# slimarm_apricot.net
KiCad netlist of a schematic drawn in EasyEDA Pro
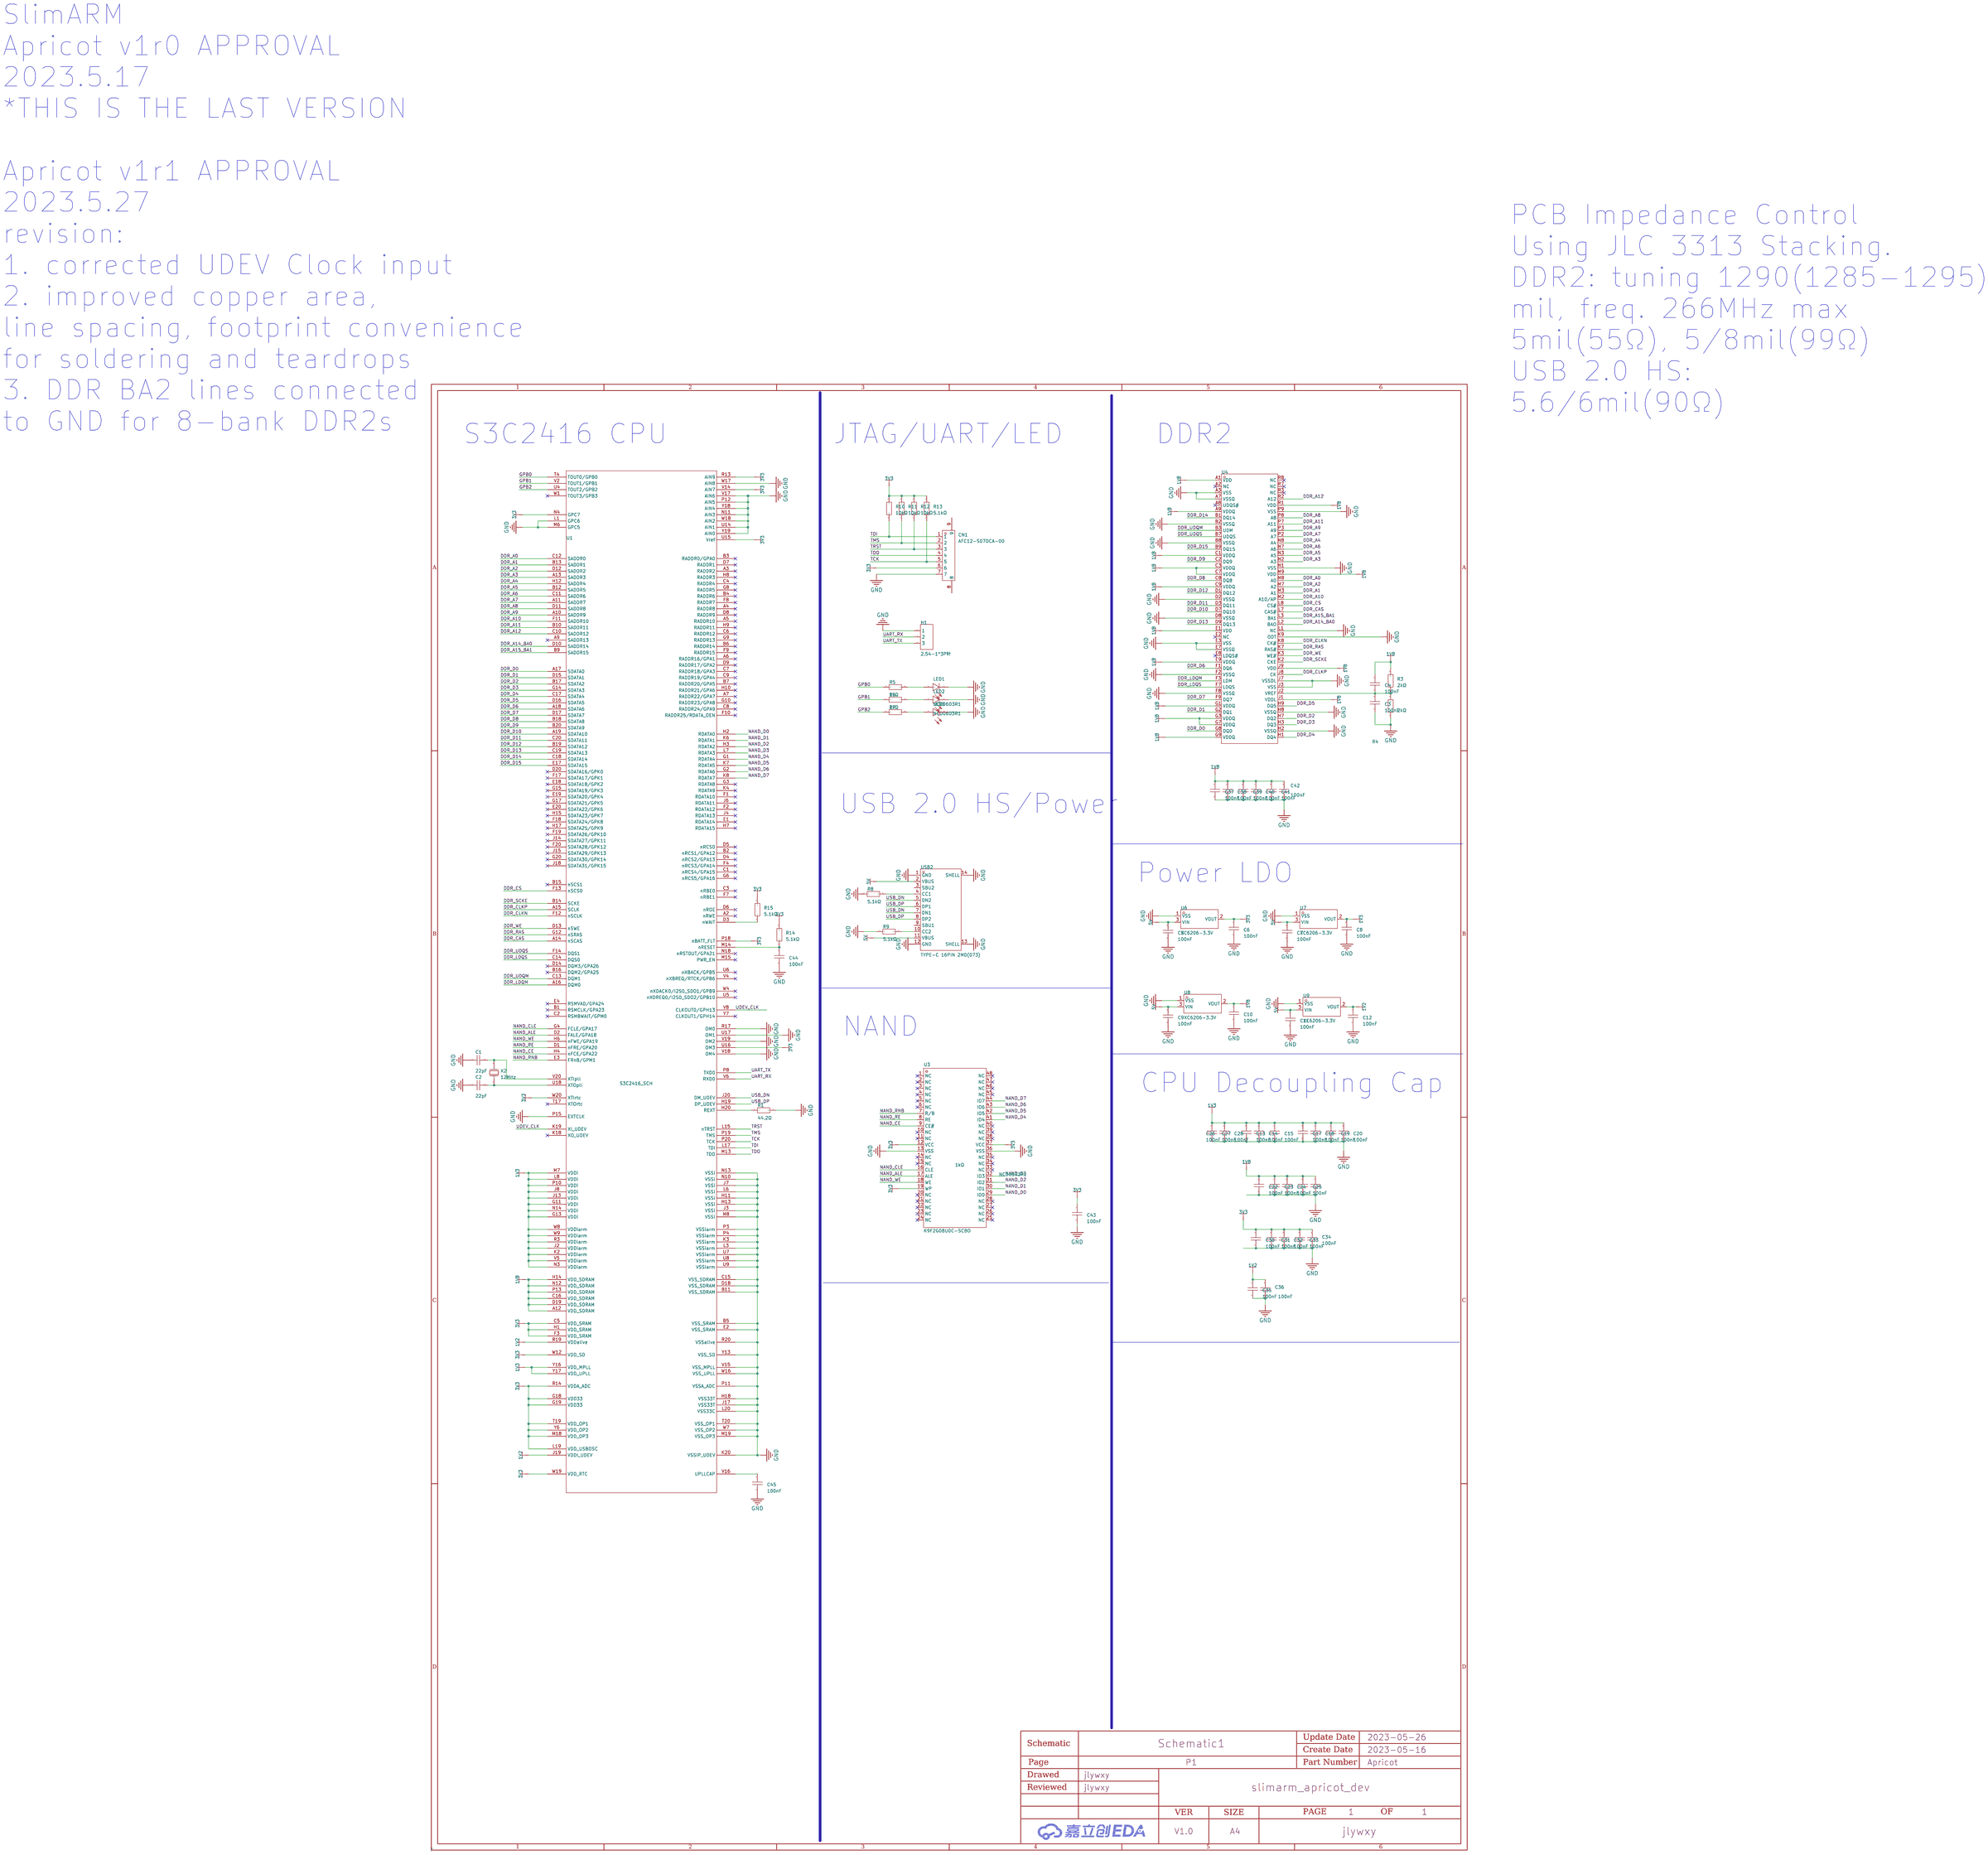
[diagram p0: schematic sheet]

(export (version "E")
  (design (tool "Eeschema 10.0.6"))
  (components
    (comp (ref "C1")
      (value "22pF")
      (footprint "easyedapro:C0402")
      (description "容值:22pF;精度:±5%;额定电压:50V;材质(温度系数):NP0;")
      (fields
        (field (name "Manufacturer Part") "CC0402JRNPO9BN220")
        (field (name "Manufacturer") "YAGEO(国巨)")
      )
      (libsource (lib "easyedapro") (part "CC0402JRNPO9BN220"))
    )
    (comp (ref "C2")
      (value "22pF")
      (footprint "easyedapro:C0402")
      (description "容值:22pF;精度:±5%;额定电压:50V;材质(温度系数):NP0;")
      (fields
        (field (name "Manufacturer Part") "CC0402JRNPO9BN220")
        (field (name "Manufacturer") "YAGEO(国巨)")
      )
      (libsource (lib "easyedapro") (part "CC0402JRNPO9BN220"))
    )
    (comp (ref "C3")
      (value "100nF")
      (footprint "easyedapro:C0402")
      (description "容值:22pF;精度:±5%;额定电压:50V;材质(温度系数):NP0;")
      (fields
        (field (name "Manufacturer Part") "CC0402JRNPO9BN220")
        (field (name "Manufacturer") "YAGEO(国巨)")
      )
      (libsource (lib "easyedapro") (part "CC0402JRNPO9BN220"))
    )
    (comp (ref "C4")
      (value "100nF")
      (footprint "easyedapro:C0402")
      (description "容值:22pF;精度:±5%;额定电压:50V;材质(温度系数):NP0;")
      (fields
        (field (name "Manufacturer Part") "CC0402JRNPO9BN220")
        (field (name "Manufacturer") "YAGEO(国巨)")
      )
      (libsource (lib "easyedapro") (part "CC0402JRNPO9BN220"))
    )
    (comp (ref "C5")
      (value "100nF")
      (footprint "easyedapro:C0402")
      (description "容值:22pF;精度:±5%;额定电压:50V;材质(温度系数):NP0;")
      (fields
        (field (name "Manufacturer Part") "CC0402JRNPO9BN220")
        (field (name "Manufacturer") "YAGEO(国巨)")
      )
      (libsource (lib "easyedapro") (part "CC0402JRNPO9BN220"))
    )
    (comp (ref "C6")
      (value "100nF")
      (footprint "easyedapro:C0402")
      (description "容值:22pF;精度:±5%;额定电压:50V;材质(温度系数):NP0;")
      (fields
        (field (name "Manufacturer Part") "CC0402JRNPO9BN220")
        (field (name "Manufacturer") "YAGEO(国巨)")
      )
      (libsource (lib "easyedapro") (part "CC0402JRNPO9BN220"))
    )
    (comp (ref "C7")
      (value "100nF")
      (footprint "easyedapro:C0402")
      (description "容值:22pF;精度:±5%;额定电压:50V;材质(温度系数):NP0;")
      (fields
        (field (name "Manufacturer Part") "CC0402JRNPO9BN220")
        (field (name "Manufacturer") "YAGEO(国巨)")
      )
      (libsource (lib "easyedapro") (part "CC0402JRNPO9BN220"))
    )
    (comp (ref "C8")
      (value "100nF")
      (footprint "easyedapro:C0402")
      (description "容值:22pF;精度:±5%;额定电压:50V;材质(温度系数):NP0;")
      (fields
        (field (name "Manufacturer Part") "CC0402JRNPO9BN220")
        (field (name "Manufacturer") "YAGEO(国巨)")
      )
      (libsource (lib "easyedapro") (part "CC0402JRNPO9BN220"))
    )
    (comp (ref "C9")
      (value "100nF")
      (footprint "easyedapro:C0402")
      (description "容值:22pF;精度:±5%;额定电压:50V;材质(温度系数):NP0;")
      (fields
        (field (name "Manufacturer Part") "CC0402JRNPO9BN220")
        (field (name "Manufacturer") "YAGEO(国巨)")
      )
      (libsource (lib "easyedapro") (part "CC0402JRNPO9BN220"))
    )
    (comp (ref "C10")
      (value "100nF")
      (footprint "easyedapro:C0402")
      (description "容值:22pF;精度:±5%;额定电压:50V;材质(温度系数):NP0;")
      (fields
        (field (name "Manufacturer Part") "CC0402JRNPO9BN220")
        (field (name "Manufacturer") "YAGEO(国巨)")
      )
      (libsource (lib "easyedapro") (part "CC0402JRNPO9BN220"))
    )
    (comp (ref "C11")
      (value "100nF")
      (footprint "easyedapro:C0402")
      (description "容值:22pF;精度:±5%;额定电压:50V;材质(温度系数):NP0;")
      (fields
        (field (name "Manufacturer Part") "CC0402JRNPO9BN220")
        (field (name "Manufacturer") "YAGEO(国巨)")
      )
      (libsource (lib "easyedapro") (part "CC0402JRNPO9BN220"))
    )
    (comp (ref "C12")
      (value "100nF")
      (footprint "easyedapro:C0402")
      (description "容值:22pF;精度:±5%;额定电压:50V;材质(温度系数):NP0;")
      (fields
        (field (name "Manufacturer Part") "CC0402JRNPO9BN220")
        (field (name "Manufacturer") "YAGEO(国巨)")
      )
      (libsource (lib "easyedapro") (part "CC0402JRNPO9BN220"))
    )
    (comp (ref "C13")
      (value "100nF")
      (footprint "easyedapro:C0402")
      (description "容值:22pF;精度:±5%;额定电压:50V;材质(温度系数):NP0;")
      (fields
        (field (name "Manufacturer Part") "CC0402JRNPO9BN220")
        (field (name "Manufacturer") "YAGEO(国巨)")
      )
      (libsource (lib "easyedapro") (part "CC0402JRNPO9BN220"))
    )
    (comp (ref "C14")
      (value "100nF")
      (footprint "easyedapro:C0402")
      (description "容值:22pF;精度:±5%;额定电压:50V;材质(温度系数):NP0;")
      (fields
        (field (name "Manufacturer Part") "CC0402JRNPO9BN220")
        (field (name "Manufacturer") "YAGEO(国巨)")
      )
      (libsource (lib "easyedapro") (part "CC0402JRNPO9BN220"))
    )
    (comp (ref "C15")
      (value "100nF")
      (footprint "easyedapro:C0402")
      (description "容值:22pF;精度:±5%;额定电压:50V;材质(温度系数):NP0;")
      (fields
        (field (name "Manufacturer Part") "CC0402JRNPO9BN220")
        (field (name "Manufacturer") "YAGEO(国巨)")
      )
      (libsource (lib "easyedapro") (part "CC0402JRNPO9BN220"))
    )
    (comp (ref "C17")
      (value "100nF")
      (footprint "easyedapro:C0402")
      (description "容值:22pF;精度:±5%;额定电压:50V;材质(温度系数):NP0;")
      (fields
        (field (name "Manufacturer Part") "CC0402JRNPO9BN220")
        (field (name "Manufacturer") "YAGEO(国巨)")
      )
      (libsource (lib "easyedapro") (part "CC0402JRNPO9BN220"))
    )
    (comp (ref "C18")
      (value "100nF")
      (footprint "easyedapro:C0402")
      (description "容值:22pF;精度:±5%;额定电压:50V;材质(温度系数):NP0;")
      (fields
        (field (name "Manufacturer Part") "CC0402JRNPO9BN220")
        (field (name "Manufacturer") "YAGEO(国巨)")
      )
      (libsource (lib "easyedapro") (part "CC0402JRNPO9BN220"))
    )
    (comp (ref "C19")
      (value "100nF")
      (footprint "easyedapro:C0402")
      (description "容值:22pF;精度:±5%;额定电压:50V;材质(温度系数):NP0;")
      (fields
        (field (name "Manufacturer Part") "CC0402JRNPO9BN220")
        (field (name "Manufacturer") "YAGEO(国巨)")
      )
      (libsource (lib "easyedapro") (part "CC0402JRNPO9BN220"))
    )
    (comp (ref "C20")
      (value "100nF")
      (footprint "easyedapro:C0402")
      (description "容值:22pF;精度:±5%;额定电压:50V;材质(温度系数):NP0;")
      (fields
        (field (name "Manufacturer Part") "CC0402JRNPO9BN220")
        (field (name "Manufacturer") "YAGEO(国巨)")
      )
      (libsource (lib "easyedapro") (part "CC0402JRNPO9BN220"))
    )
    (comp (ref "C22")
      (value "100nF")
      (footprint "easyedapro:C0402")
      (description "容值:22pF;精度:±5%;额定电压:50V;材质(温度系数):NP0;")
      (fields
        (field (name "Manufacturer Part") "CC0402JRNPO9BN220")
        (field (name "Manufacturer") "YAGEO(国巨)")
      )
      (libsource (lib "easyedapro") (part "CC0402JRNPO9BN220"))
    )
    (comp (ref "C23")
      (value "100nF")
      (footprint "easyedapro:C0402")
      (description "容值:22pF;精度:±5%;额定电压:50V;材质(温度系数):NP0;")
      (fields
        (field (name "Manufacturer Part") "CC0402JRNPO9BN220")
        (field (name "Manufacturer") "YAGEO(国巨)")
      )
      (libsource (lib "easyedapro") (part "CC0402JRNPO9BN220"))
    )
    (comp (ref "C24")
      (value "100nF")
      (footprint "easyedapro:C0402")
      (description "容值:22pF;精度:±5%;额定电压:50V;材质(温度系数):NP0;")
      (fields
        (field (name "Manufacturer Part") "CC0402JRNPO9BN220")
        (field (name "Manufacturer") "YAGEO(国巨)")
      )
      (libsource (lib "easyedapro") (part "CC0402JRNPO9BN220"))
    )
    (comp (ref "C25")
      (value "100nF")
      (footprint "easyedapro:C0402")
      (description "容值:22pF;精度:±5%;额定电压:50V;材质(温度系数):NP0;")
      (fields
        (field (name "Manufacturer Part") "CC0402JRNPO9BN220")
        (field (name "Manufacturer") "YAGEO(国巨)")
      )
      (libsource (lib "easyedapro") (part "CC0402JRNPO9BN220"))
    )
    (comp (ref "C26")
      (value "100nF")
      (footprint "easyedapro:C0402")
      (description "容值:22pF;精度:±5%;额定电压:50V;材质(温度系数):NP0;")
      (fields
        (field (name "Manufacturer Part") "CC0402JRNPO9BN220")
        (field (name "Manufacturer") "YAGEO(国巨)")
      )
      (libsource (lib "easyedapro") (part "CC0402JRNPO9BN220"))
    )
    (comp (ref "C27")
      (value "100nF")
      (footprint "easyedapro:C0402")
      (description "容值:22pF;精度:±5%;额定电压:50V;材质(温度系数):NP0;")
      (fields
        (field (name "Manufacturer Part") "CC0402JRNPO9BN220")
        (field (name "Manufacturer") "YAGEO(国巨)")
      )
      (libsource (lib "easyedapro") (part "CC0402JRNPO9BN220"))
    )
    (comp (ref "C28")
      (value "100nF")
      (footprint "easyedapro:C0402")
      (description "容值:22pF;精度:±5%;额定电压:50V;材质(温度系数):NP0;")
      (fields
        (field (name "Manufacturer Part") "CC0402JRNPO9BN220")
        (field (name "Manufacturer") "YAGEO(国巨)")
      )
      (libsource (lib "easyedapro") (part "CC0402JRNPO9BN220"))
    )
    (comp (ref "C30")
      (value "100nF")
      (footprint "easyedapro:C0402")
      (description "容值:22pF;精度:±5%;额定电压:50V;材质(温度系数):NP0;")
      (fields
        (field (name "Manufacturer Part") "CC0402JRNPO9BN220")
        (field (name "Manufacturer") "YAGEO(国巨)")
      )
      (libsource (lib "easyedapro") (part "CC0402JRNPO9BN220"))
    )
    (comp (ref "C31")
      (value "100nF")
      (footprint "easyedapro:C0402")
      (description "容值:22pF;精度:±5%;额定电压:50V;材质(温度系数):NP0;")
      (fields
        (field (name "Manufacturer Part") "CC0402JRNPO9BN220")
        (field (name "Manufacturer") "YAGEO(国巨)")
      )
      (libsource (lib "easyedapro") (part "CC0402JRNPO9BN220"))
    )
    (comp (ref "C32")
      (value "100nF")
      (footprint "easyedapro:C0402")
      (description "容值:22pF;精度:±5%;额定电压:50V;材质(温度系数):NP0;")
      (fields
        (field (name "Manufacturer Part") "CC0402JRNPO9BN220")
        (field (name "Manufacturer") "YAGEO(国巨)")
      )
      (libsource (lib "easyedapro") (part "CC0402JRNPO9BN220"))
    )
    (comp (ref "C33")
      (value "100nF")
      (footprint "easyedapro:C0402")
      (description "容值:22pF;精度:±5%;额定电压:50V;材质(温度系数):NP0;")
      (fields
        (field (name "Manufacturer Part") "CC0402JRNPO9BN220")
        (field (name "Manufacturer") "YAGEO(国巨)")
      )
      (libsource (lib "easyedapro") (part "CC0402JRNPO9BN220"))
    )
    (comp (ref "C34")
      (value "100nF")
      (footprint "easyedapro:C0402")
      (description "容值:22pF;精度:±5%;额定电压:50V;材质(温度系数):NP0;")
      (fields
        (field (name "Manufacturer Part") "CC0402JRNPO9BN220")
        (field (name "Manufacturer") "YAGEO(国巨)")
      )
      (libsource (lib "easyedapro") (part "CC0402JRNPO9BN220"))
    )
    (comp (ref "C35")
      (value "100nF")
      (footprint "easyedapro:C0402")
      (description "容值:22pF;精度:±5%;额定电压:50V;材质(温度系数):NP0;")
      (fields
        (field (name "Manufacturer Part") "CC0402JRNPO9BN220")
        (field (name "Manufacturer") "YAGEO(国巨)")
      )
      (libsource (lib "easyedapro") (part "CC0402JRNPO9BN220"))
    )
    (comp (ref "C36")
      (value "100nF")
      (footprint "easyedapro:C0402")
      (description "容值:22pF;精度:±5%;额定电压:50V;材质(温度系数):NP0;")
      (fields
        (field (name "Manufacturer Part") "CC0402JRNPO9BN220")
        (field (name "Manufacturer") "YAGEO(国巨)")
      )
      (libsource (lib "easyedapro") (part "CC0402JRNPO9BN220"))
    )
    (comp (ref "C37")
      (value "100nF")
      (footprint "easyedapro:C0402")
      (description "容值:22pF;精度:±5%;额定电压:50V;材质(温度系数):NP0;")
      (fields
        (field (name "Manufacturer Part") "CC0402JRNPO9BN220")
        (field (name "Manufacturer") "YAGEO(国巨)")
      )
      (libsource (lib "easyedapro") (part "CC0402JRNPO9BN220"))
    )
    (comp (ref "C38")
      (value "100nF")
      (footprint "easyedapro:C0402")
      (description "容值:22pF;精度:±5%;额定电压:50V;材质(温度系数):NP0;")
      (fields
        (field (name "Manufacturer Part") "CC0402JRNPO9BN220")
        (field (name "Manufacturer") "YAGEO(国巨)")
      )
      (libsource (lib "easyedapro") (part "CC0402JRNPO9BN220"))
    )
    (comp (ref "C39")
      (value "100nF")
      (footprint "easyedapro:C0402")
      (description "容值:22pF;精度:±5%;额定电压:50V;材质(温度系数):NP0;")
      (fields
        (field (name "Manufacturer Part") "CC0402JRNPO9BN220")
        (field (name "Manufacturer") "YAGEO(国巨)")
      )
      (libsource (lib "easyedapro") (part "CC0402JRNPO9BN220"))
    )
    (comp (ref "C40")
      (value "100nF")
      (footprint "easyedapro:C0402")
      (description "容值:22pF;精度:±5%;额定电压:50V;材质(温度系数):NP0;")
      (fields
        (field (name "Manufacturer Part") "CC0402JRNPO9BN220")
        (field (name "Manufacturer") "YAGEO(国巨)")
      )
      (libsource (lib "easyedapro") (part "CC0402JRNPO9BN220"))
    )
    (comp (ref "C41")
      (value "100nF")
      (footprint "easyedapro:C0402")
      (description "容值:22pF;精度:±5%;额定电压:50V;材质(温度系数):NP0;")
      (fields
        (field (name "Manufacturer Part") "CC0402JRNPO9BN220")
        (field (name "Manufacturer") "YAGEO(国巨)")
      )
      (libsource (lib "easyedapro") (part "CC0402JRNPO9BN220"))
    )
    (comp (ref "C42")
      (value "100nF")
      (footprint "easyedapro:C0402")
      (description "容值:22pF;精度:±5%;额定电压:50V;材质(温度系数):NP0;")
      (fields
        (field (name "Manufacturer Part") "CC0402JRNPO9BN220")
        (field (name "Manufacturer") "YAGEO(国巨)")
      )
      (libsource (lib "easyedapro") (part "CC0402JRNPO9BN220"))
    )
    (comp (ref "C43")
      (value "100nF")
      (footprint "easyedapro:C0402")
      (description "容值:22pF;精度:±5%;额定电压:50V;材质(温度系数):NP0;")
      (fields
        (field (name "Manufacturer Part") "CC0402JRNPO9BN220")
        (field (name "Manufacturer") "YAGEO(国巨)")
      )
      (libsource (lib "easyedapro") (part "CC0402JRNPO9BN220"))
    )
    (comp (ref "C44")
      (value "100nF")
      (footprint "easyedapro:C0402")
      (description "容值:22pF;精度:±5%;额定电压:50V;材质(温度系数):NP0;")
      (fields
        (field (name "Manufacturer Part") "CC0402JRNPO9BN220")
        (field (name "Manufacturer") "YAGEO(国巨)")
      )
      (libsource (lib "easyedapro") (part "CC0402JRNPO9BN220"))
    )
    (comp (ref "C45")
      (value "100nF")
      (footprint "easyedapro:C0402")
      (description "容值:22pF;精度:±5%;额定电压:50V;材质(温度系数):NP0;")
      (fields
        (field (name "Manufacturer Part") "CC0402JRNPO9BN220")
        (field (name "Manufacturer") "YAGEO(国巨)")
      )
      (libsource (lib "easyedapro") (part "CC0402JRNPO9BN220"))
    )
    (comp (ref "CN1")
      (value "AFC12-S07DCA-00")
      (footprint "easyedapro:CONN-SMD_AFC12-S07DCA-00")
      (description "参考系列:-;间距:1.25mm;插针结构:1x7P;排数:1;每排PIN数:7;行距:-;公母:公型插针;安装方式:卧贴;额定电流:1A;工作温度范围:-20°C~+85°C;")
      (fields (field (name "Manufacturer") "JS(钜硕电子)"))
      (libsource (lib "easyedapro") (part "AFC12-S07DCA-00"))
    )
    (comp (ref "H1")
      (value "2.54-1*3P针")
      (footprint "easyedapro:HDR-TH_3P-P2.54-V-M-1")
      (fields (field (name "Manufacturer") "BOOMELE(博穆精密)"))
      (libsource (lib "easyedapro") (part "Header-Male-2.54_1x3"))
    )
    (comp (ref "LED1")
      (value "NCD0603R1")
      (footprint "easyedapro:LED0603-RD_RED")
      (description "发光颜色:红灯;")
      (fields (field (name "Manufacturer") "国星光电"))
      (libsource (lib "easyedapro") (part "FC-DA1608HRK-620D"))
    )
    (comp (ref "LED2")
      (value "NCD0603R1")
      (footprint "easyedapro:LED0603-RD_RED")
      (description "发光颜色:红灯;")
      (fields (field (name "Manufacturer") "国星光电"))
      (libsource (lib "easyedapro") (part "FC-DA1608HRK-620D"))
    )
    (comp (ref "LED3")
      (value "NCD0603R1")
      (footprint "easyedapro:LED0603-RD_RED")
      (description "发光颜色:红灯;")
      (fields (field (name "Manufacturer") "国星光电"))
      (libsource (lib "easyedapro") (part "FC-DA1608HRK-620D"))
    )
    (comp (ref "R1")
      (value "44.2Ω")
      (footprint "easyedapro:R0402")
      (description "阻值:44.2Ω;精度:±1%;功率:62.5mW;")
      (fields (field (name "Manufacturer Part") "RCT0244R2FLF") (field (name "Manufacturer") "HKR"))
      (libsource (lib "easyedapro") (part "RCT0244R2FLF"))
    )
    (comp (ref "R3")
      (value "2kΩ")
      (footprint "easyedapro:R0402")
      (description "阻值:44.2Ω;精度:±1%;功率:62.5mW;")
      (fields (field (name "Manufacturer Part") "RCT0244R2FLF") (field (name "Manufacturer") "HKR"))
      (libsource (lib "easyedapro") (part "RCT0244R2FLF"))
    )
    (comp (ref "R4")
      (value "2kΩ")
      (footprint "easyedapro:R0402")
      (description "阻值:44.2Ω;精度:±1%;功率:62.5mW;")
      (fields (field (name "Manufacturer Part") "RCT0244R2FLF") (field (name "Manufacturer") "HKR"))
      (libsource (lib "easyedapro") (part "RCT0244R2FLF"))
    )
    (comp (ref "R5")
      (value "1kΩ")
      (footprint "easyedapro:R0603")
      (description "电阻类型:厚膜电阻;阻值:1kΩ;精度:±1%;功率:100mW;")
      (fields
        (field (name "Manufacturer Part") "0603WAF1001T5E")
        (field (name "Manufacturer") "UNI-ROYAL(厚声)")
      )
      (libsource (lib "easyedapro") (part "0603WAF1001T5E"))
    )
    (comp (ref "R6")
      (value "1kΩ")
      (footprint "easyedapro:R0603")
      (description "电阻类型:厚膜电阻;阻值:1kΩ;精度:±1%;功率:100mW;")
      (fields
        (field (name "Manufacturer Part") "0603WAF1001T5E")
        (field (name "Manufacturer") "UNI-ROYAL(厚声)")
      )
      (libsource (lib "easyedapro") (part "0603WAF1001T5E"))
    )
    (comp (ref "R7")
      (value "1kΩ")
      (footprint "easyedapro:R0603")
      (description "电阻类型:厚膜电阻;阻值:1kΩ;精度:±1%;功率:100mW;")
      (fields
        (field (name "Manufacturer Part") "0603WAF1001T5E")
        (field (name "Manufacturer") "UNI-ROYAL(厚声)")
      )
      (libsource (lib "easyedapro") (part "0603WAF1001T5E"))
    )
    (comp (ref "R8")
      (value "5.1kΩ")
      (footprint "easyedapro:R0402")
      (description "电阻类型:厚膜电阻;阻值:5.1kΩ;精度:±1%;功率:62.5mW;")
      (fields
        (field (name "Manufacturer Part") "0402WGF5101TCE")
        (field (name "Manufacturer") "UNI-ROYAL(厚声)")
      )
      (libsource (lib "easyedapro") (part "0402WGF5101TCE"))
    )
    (comp (ref "R9")
      (value "5.1kΩ")
      (footprint "easyedapro:R0402")
      (description "电阻类型:厚膜电阻;阻值:5.1kΩ;精度:±1%;功率:62.5mW;")
      (fields
        (field (name "Manufacturer Part") "0402WGF5101TCE")
        (field (name "Manufacturer") "UNI-ROYAL(厚声)")
      )
      (libsource (lib "easyedapro") (part "0402WGF5101TCE"))
    )
    (comp (ref "R10")
      (value "10kΩ")
      (footprint "easyedapro:R0402")
      (description "电阻类型:厚膜电阻;阻值:5.1kΩ;精度:±1%;功率:62.5mW;")
      (fields
        (field (name "Manufacturer Part") "0402WGF5101TCE")
        (field (name "Manufacturer") "UNI-ROYAL(厚声)")
      )
      (libsource (lib "easyedapro") (part "0402WGF5101TCE"))
    )
    (comp (ref "R11")
      (value "10kΩ")
      (footprint "easyedapro:R0402")
      (description "电阻类型:厚膜电阻;阻值:5.1kΩ;精度:±1%;功率:62.5mW;")
      (fields
        (field (name "Manufacturer Part") "0402WGF5101TCE")
        (field (name "Manufacturer") "UNI-ROYAL(厚声)")
      )
      (libsource (lib "easyedapro") (part "0402WGF5101TCE"))
    )
    (comp (ref "R12")
      (value "10kΩ")
      (footprint "easyedapro:R0402")
      (description "电阻类型:厚膜电阻;阻值:5.1kΩ;精度:±1%;功率:62.5mW;")
      (fields
        (field (name "Manufacturer Part") "0402WGF5101TCE")
        (field (name "Manufacturer") "UNI-ROYAL(厚声)")
      )
      (libsource (lib "easyedapro") (part "0402WGF5101TCE"))
    )
    (comp (ref "R13")
      (value "5.1kΩ")
      (footprint "easyedapro:R0402")
      (description "电阻类型:厚膜电阻;阻值:5.1kΩ;精度:±1%;功率:62.5mW;")
      (fields
        (field (name "Manufacturer Part") "0402WGF5101TCE")
        (field (name "Manufacturer") "UNI-ROYAL(厚声)")
      )
      (libsource (lib "easyedapro") (part "0402WGF5101TCE"))
    )
    (comp (ref "R14")
      (value "5.1kΩ")
      (footprint "easyedapro:R0402")
      (description "电阻类型:厚膜电阻;阻值:5.1kΩ;精度:±1%;功率:62.5mW;")
      (fields
        (field (name "Manufacturer Part") "0402WGF5101TCE")
        (field (name "Manufacturer") "UNI-ROYAL(厚声)")
      )
      (libsource (lib "easyedapro") (part "0402WGF5101TCE"))
    )
    (comp (ref "R15")
      (value "5.1kΩ")
      (footprint "easyedapro:R0402")
      (description "电阻类型:厚膜电阻;阻值:5.1kΩ;精度:±1%;功率:62.5mW;")
      (fields
        (field (name "Manufacturer Part") "0402WGF5101TCE")
        (field (name "Manufacturer") "UNI-ROYAL(厚声)")
      )
      (libsource (lib "easyedapro") (part "0402WGF5101TCE"))
    )
    (comp (ref "U1") (value "S3C2416_SCH") (libsource (lib "easyedapro") (part "S3C2416_SCH")))
    (comp (ref "U3")
      (value "K9F2G08U0C-SCBO")
      (footprint "easyedapro:TSOP-48_L12.0-W18.4-P0.50-LS20.0-BL")
      (description "存储器构架(格式):FLASH;存储器接口类型:Parallel;存储器容量:2Gb (256M x 8);存储器类型:Non-Volatile;")
      (libsource (lib "easyedapro") (part "K9F2G08UOC-SCBO"))
    )
    (comp (ref "U4")
      (value "NT5TU32M16FG-AC")
      (footprint "easyedapro:VFBGA-84_L7.5-W12.2-P0.80-TL_NANYA_NT5TU32M16FG")
      (fields (field (name "Manufacturer") "Nanya(南亚科技)"))
      (libsource (lib "easyedapro") (part "NT5TU32M16FG-AC"))
    )
    (comp (ref "U6")
      (value "XC6206-3.3V")
      (footprint "easyedapro:SSOT-3_L2.9-W1.6-P0.95-LS2.8-BR")
      (description "输出类型:固定;输出极性:正;最大输入电压:6V;输出电压:3.3V;输出电流:250mA;")
      (fields (field (name "Manufacturer") "YONGYUTAI(永裕泰)"))
      (libsource (lib "easyedapro") (part "XC6206-3.3V"))
    )
    (comp (ref "U7")
      (value "XC6206-3.3V")
      (footprint "easyedapro:SSOT-3_L2.9-W1.6-P0.95-LS2.8-BR")
      (description "输出类型:固定;输出极性:正;最大输入电压:6V;输出电压:3.3V;输出电流:250mA;")
      (fields (field (name "Manufacturer") "YONGYUTAI(永裕泰)"))
      (libsource (lib "easyedapro") (part "XC6206-3.3V"))
    )
    (comp (ref "U8")
      (value "XC6206-3.3V")
      (footprint "easyedapro:SSOT-3_L2.9-W1.6-P0.95-LS2.8-BR")
      (description "输出类型:固定;输出极性:正;最大输入电压:6V;输出电压:3.3V;输出电流:250mA;")
      (fields (field (name "Manufacturer") "YONGYUTAI(永裕泰)"))
      (libsource (lib "easyedapro") (part "XC6206-3.3V"))
    )
    (comp (ref "U9")
      (value "XC6206-3.3V")
      (footprint "easyedapro:SSOT-3_L2.9-W1.6-P0.95-LS2.8-BR")
      (description "输出类型:固定;输出极性:正;最大输入电压:6V;输出电压:3.3V;输出电流:250mA;")
      (fields (field (name "Manufacturer") "YONGYUTAI(永裕泰)"))
      (libsource (lib "easyedapro") (part "XC6206-3.3V"))
    )
    (comp (ref "USB2")
      (value "TYPE-C 16PIN 2MD(073)")
      (footprint "easyedapro:USB-C-SMD_TYPE-C-6PIN-2MD-073")
      (description "连接器类型:Type-C;标准:-;公母:母座;触点数量:16;端口数量:1;安装方式:卧贴;额定电流 - 电源:5A;工作温度范围:-25°C~+85°C;")
      (fields (field (name "Manufacturer") "SHOU HAN(首韩)"))
      (libsource (lib "easyedapro") (part "TYPE-C 16PIN 2MD(073)"))
    )
    (comp (ref "X2")
      (value "12MHz")
      (footprint "easyedapro:CRYSTAL-SMD_L5.0-W3.2")
      (description "频率:8MHz;频率公差:±10ppm;负载电容:20pF;")
      (fields (field (name "Manufacturer Part") "X50328MSB2GI") (field (name "Manufacturer") "YXC(扬兴晶振)"))
      (libsource (lib "easyedapro") (part "X50328MSB2GI"))
    )
  )
  (nets
    (net (code "1") (name "/DDR_A0") (class "Default")
      (node (ref "U1") (pin "C12") (pinfunction "SADDR0_C12") (pintype "input"))
      (node (ref "U4") (pin "M8") (pinfunction "A0_M8") (pintype "input"))
    )
    (net (code "2") (name "/DDR_A1") (class "Default")
      (node (ref "U1") (pin "B13") (pinfunction "SADDR1_B13") (pintype "input"))
      (node (ref "U4") (pin "M3") (pinfunction "A1_M3") (pintype "input"))
    )
    (net (code "3") (name "/DDR_A2") (class "Default")
      (node (ref "U1") (pin "D12") (pinfunction "SADDR2_D12") (pintype "input"))
      (node (ref "U4") (pin "M7") (pinfunction "A2_M7") (pintype "input"))
    )
    (net (code "4") (name "/DDR_A3") (class "Default")
      (node (ref "U1") (pin "A13") (pinfunction "SADDR3_A13") (pintype "input"))
      (node (ref "U4") (pin "N2") (pinfunction "A3_N2") (pintype "input"))
    )
    (net (code "5") (name "/DDR_A4") (class "Default")
      (node (ref "U1") (pin "H12") (pinfunction "SADDR4_H12") (pintype "input"))
      (node (ref "U4") (pin "N8") (pinfunction "A4_N8") (pintype "input"))
    )
    (net (code "6") (name "/DDR_A5") (class "Default")
      (node (ref "U1") (pin "B12") (pinfunction "SADDR5_B12") (pintype "input"))
      (node (ref "U4") (pin "N3") (pinfunction "A5_N3") (pintype "input"))
    )
    (net (code "7") (name "/DDR_A6") (class "Default")
      (node (ref "U1") (pin "C11") (pinfunction "SADDR6_C11") (pintype "input"))
      (node (ref "U4") (pin "N7") (pinfunction "A6_N7") (pintype "input"))
    )
    (net (code "8") (name "/DDR_A7") (class "Default")
      (node (ref "U1") (pin "A11") (pinfunction "SADDR7_A11") (pintype "input"))
      (node (ref "U4") (pin "P2") (pinfunction "A7_P2") (pintype "input"))
    )
    (net (code "9") (name "/DDR_A8") (class "Default")
      (node (ref "U1") (pin "D11") (pinfunction "SADDR8_D11") (pintype "input"))
      (node (ref "U4") (pin "P8") (pinfunction "A8_P8") (pintype "input"))
    )
    (net (code "10") (name "/DDR_A9") (class "Default")
      (node (ref "U1") (pin "A10") (pinfunction "SADDR9_A10") (pintype "input"))
      (node (ref "U4") (pin "P3") (pinfunction "A9_P3") (pintype "input"))
    )
    (net (code "11") (name "/DDR_A10") (class "Default")
      (node (ref "U1") (pin "F11") (pinfunction "SADDR10_F11") (pintype "input"))
      (node (ref "U4") (pin "M2") (pinfunction "A10/AP_M2") (pintype "input"))
    )
    (net (code "12") (name "/DDR_A11") (class "Default")
      (node (ref "U1") (pin "B10") (pinfunction "SADDR11_B10") (pintype "input"))
      (node (ref "U4") (pin "P7") (pinfunction "A11_P7") (pintype "input"))
    )
    (net (code "13") (name "/DDR_A12") (class "Default")
      (node (ref "U1") (pin "C10") (pinfunction "SADDR12_C10") (pintype "input"))
      (node (ref "U4") (pin "R2") (pinfunction "A12_R2") (pintype "input"))
    )
    (net (code "14") (name "/DDR_A14_BA0") (class "Default")
      (node (ref "U1") (pin "D10") (pinfunction "SADDR14_D10") (pintype "input"))
      (node (ref "U4") (pin "L2") (pinfunction "BAO_L2") (pintype "input"))
    )
    (net (code "15") (name "/DDR_A15_BA1") (class "Default")
      (node (ref "U1") (pin "B9") (pinfunction "SADDR15_B9") (pintype "input"))
      (node (ref "U4") (pin "L3") (pinfunction "BA1_L3") (pintype "input"))
    )
    (net (code "16") (name "/DDR_CAS") (class "Default")
      (node (ref "U1") (pin "A14") (pinfunction "nSCAS_A14") (pintype "input"))
      (node (ref "U4") (pin "L7") (pinfunction "CAS#_L7") (pintype "input"))
    )
    (net (code "17") (name "/DDR_CLKN") (class "Default")
      (node (ref "U1") (pin "F12") (pinfunction "nSCLK_F12") (pintype "input"))
      (node (ref "U4") (pin "K8") (pinfunction "CK#_K8") (pintype "input"))
    )
    (net (code "18") (name "/DDR_CLKP") (class "Default")
      (node (ref "U1") (pin "A15") (pinfunction "SCLK_A15") (pintype "input"))
      (node (ref "U4") (pin "J8") (pinfunction "CK_J8") (pintype "input"))
    )
    (net (code "19") (name "/DDR_CS") (class "Default")
      (node (ref "U1") (pin "F13") (pinfunction "nSCS0_F13") (pintype "input"))
      (node (ref "U4") (pin "L8") (pinfunction "CS#_L8") (pintype "input"))
    )
    (net (code "20") (name "/DDR_D0") (class "Default")
      (node (ref "U1") (pin "A17") (pinfunction "SDATA0_A17") (pintype "input"))
      (node (ref "U4") (pin "G8") (pinfunction "DQ0_G8") (pintype "input"))
    )
    (net (code "21") (name "/DDR_D1") (class "Default")
      (node (ref "U1") (pin "D15") (pinfunction "SDATA1_D15") (pintype "input"))
      (node (ref "U4") (pin "G2") (pinfunction "DQ1_G2") (pintype "input"))
    )
    (net (code "22") (name "/DDR_D2") (class "Default")
      (node (ref "U1") (pin "B17") (pinfunction "SDATA2_B17") (pintype "input"))
      (node (ref "U4") (pin "H7") (pinfunction "DQ2_H7") (pintype "input"))
    )
    (net (code "23") (name "/DDR_D3") (class "Default")
      (node (ref "U1") (pin "G14") (pinfunction "SDATA3_G14") (pintype "input"))
      (node (ref "U4") (pin "H3") (pinfunction "DQ3_H3") (pintype "input"))
    )
    (net (code "24") (name "/DDR_D4") (class "Default")
      (node (ref "U1") (pin "C17") (pinfunction "SDATA4_C17") (pintype "input"))
      (node (ref "U4") (pin "H1") (pinfunction "DQ4_H1") (pintype "input"))
    )
    (net (code "25") (name "/DDR_D5") (class "Default")
      (node (ref "U1") (pin "D16") (pinfunction "SDATA5_D16") (pintype "input"))
      (node (ref "U4") (pin "H9") (pinfunction "DQ5_H9") (pintype "input"))
    )
    (net (code "26") (name "/DDR_D6") (class "Default")
      (node (ref "U1") (pin "A18") (pinfunction "SDATA6_A18") (pintype "input"))
      (node (ref "U4") (pin "F1") (pinfunction "DQ6_F1") (pintype "input"))
    )
    (net (code "27") (name "/DDR_D7") (class "Default")
      (node (ref "U1") (pin "D17") (pinfunction "SDATA7_D17") (pintype "input"))
      (node (ref "U4") (pin "F9") (pinfunction "DQ7_F9") (pintype "input"))
    )
    (net (code "28") (name "/DDR_D8") (class "Default")
      (node (ref "U1") (pin "B18") (pinfunction "SDATA8_B18") (pintype "input"))
      (node (ref "U4") (pin "C8") (pinfunction "DQ8_C8") (pintype "input"))
    )
    (net (code "29") (name "/DDR_D9") (class "Default")
      (node (ref "U1") (pin "B20") (pinfunction "SDATA9_B20") (pintype "input"))
      (node (ref "U4") (pin "C2") (pinfunction "DQ9_C2") (pintype "input"))
    )
    (net (code "30") (name "/DDR_D10") (class "Default")
      (node (ref "U1") (pin "A19") (pinfunction "SDATA10_A19") (pintype "input"))
      (node (ref "U4") (pin "D7") (pinfunction "DQ10_D7") (pintype "input"))
    )
    (net (code "31") (name "/DDR_D11") (class "Default")
      (node (ref "U1") (pin "C20") (pinfunction "SDATA11_C20") (pintype "input"))
      (node (ref "U4") (pin "D3") (pinfunction "DQ11_D3") (pintype "input"))
    )
    (net (code "32") (name "/DDR_D12") (class "Default")
      (node (ref "U1") (pin "B19") (pinfunction "SDATA12_B19") (pintype "input"))
      (node (ref "U4") (pin "D1") (pinfunction "DQ12_D1") (pintype "input"))
    )
    (net (code "33") (name "/DDR_D13") (class "Default")
      (node (ref "U1") (pin "C19") (pinfunction "SDATA13_C19") (pintype "input"))
      (node (ref "U4") (pin "D9") (pinfunction "DQ13_D9") (pintype "input"))
    )
    (net (code "34") (name "/DDR_D14") (class "Default")
      (node (ref "U1") (pin "C18") (pinfunction "SDATA14_C18") (pintype "input"))
      (node (ref "U4") (pin "B1") (pinfunction "DQ14_B1") (pintype "input"))
    )
    (net (code "35") (name "/DDR_D15") (class "Default")
      (node (ref "U1") (pin "E17") (pinfunction "SDATA15_E17") (pintype "input"))
      (node (ref "U4") (pin "B9") (pinfunction "DQ15_B9") (pintype "input"))
    )
    (net (code "36") (name "/DDR_LDQM") (class "Default")
      (node (ref "U1") (pin "A16") (pinfunction "DQM0_A16") (pintype "input"))
      (node (ref "U4") (pin "F3") (pinfunction "LDM_F3") (pintype "input"))
    )
    (net (code "37") (name "/DDR_LDQS") (class "Default")
      (node (ref "U1") (pin "C14") (pinfunction "DQS0_C14") (pintype "input"))
      (node (ref "U4") (pin "F7") (pinfunction "LDQS_F7") (pintype "input"))
    )
    (net (code "38") (name "/DDR_RAS") (class "Default")
      (node (ref "U1") (pin "G12") (pinfunction "nSRAS_G12") (pintype "input"))
      (node (ref "U4") (pin "K7") (pinfunction "RAS#_K7") (pintype "input"))
    )
    (net (code "39") (name "/DDR_SCKE") (class "Default")
      (node (ref "U1") (pin "B14") (pinfunction "SCKE_B14") (pintype "input"))
      (node (ref "U4") (pin "K2") (pinfunction "CKE_K2") (pintype "input"))
    )
    (net (code "40") (name "/DDR_UDQM") (class "Default")
      (node (ref "U1") (pin "C13") (pinfunction "DQM1_C13") (pintype "input"))
      (node (ref "U4") (pin "B3") (pinfunction "UDM_B3") (pintype "input"))
    )
    (net (code "41") (name "/DDR_UDQS") (class "Default")
      (node (ref "U1") (pin "F14") (pinfunction "DQS1_F14") (pintype "input"))
      (node (ref "U4") (pin "B7") (pinfunction "UDQS_B7") (pintype "input"))
    )
    (net (code "42") (name "/DDR_WE") (class "Default")
      (node (ref "U1") (pin "D13") (pinfunction "nSWE_D13") (pintype "input"))
      (node (ref "U4") (pin "K3") (pinfunction "WE#_K3") (pintype "input"))
    )
    (net (code "43") (name "/GPB0") (class "Default")
      (node (ref "R5") (pin "1") (pinfunction "1_1") (pintype "input"))
      (node (ref "U1") (pin "T4") (pinfunction "TOUT0/GPB0_T4") (pintype "input"))
    )
    (net (code "44") (name "/GPB1") (class "Default")
      (node (ref "R6") (pin "1") (pinfunction "1_1") (pintype "input"))
      (node (ref "U1") (pin "V2") (pinfunction "TOUT1/GPB1_V2") (pintype "input"))
    )
    (net (code "45") (name "/GPB2") (class "Default")
      (node (ref "R7") (pin "1") (pinfunction "1_1") (pintype "input"))
      (node (ref "U1") (pin "U4") (pinfunction "TOUT2/GPB2_U4") (pintype "input"))
    )
    (net (code "46") (name "/NAND_ALE") (class "Default")
      (node (ref "U1") (pin "D2") (pinfunction "FALE/GPA18_D2") (pintype "input"))
      (node (ref "U3") (pin "17") (pinfunction "ALE_17") (pintype "input"))
    )
    (net (code "47") (name "/NAND_CE") (class "Default")
      (node (ref "U1") (pin "H4") (pinfunction "nFCE/GPA22_H4") (pintype "input"))
      (node (ref "U3") (pin "9") (pinfunction "CE#_9") (pintype "input"))
    )
    (net (code "48") (name "/NAND_CLE") (class "Default")
      (node (ref "U1") (pin "G4") (pinfunction "FCLE/GPA17_G4") (pintype "input"))
      (node (ref "U3") (pin "16") (pinfunction "CLE_16") (pintype "input"))
    )
    (net (code "49") (name "/NAND_D0") (class "Default")
      (node (ref "U1") (pin "H2") (pinfunction "RDATA0_H2") (pintype "input"))
      (node (ref "U3") (pin "29") (pinfunction "IO0_29") (pintype "input"))
    )
    (net (code "50") (name "/NAND_D1") (class "Default")
      (node (ref "U1") (pin "K6") (pinfunction "RDATA1_K6") (pintype "input"))
      (node (ref "U3") (pin "30") (pinfunction "IO1_30") (pintype "input"))
    )
    (net (code "51") (name "/NAND_D2") (class "Default")
      (node (ref "U1") (pin "H3") (pinfunction "RDATA2_H3") (pintype "input"))
      (node (ref "U3") (pin "31") (pinfunction "IO2_31") (pintype "input"))
    )
    (net (code "52") (name "/NAND_D3") (class "Default")
      (node (ref "U1") (pin "L7") (pinfunction "RDATA3_L7") (pintype "input"))
      (node (ref "U3") (pin "32") (pinfunction "IO3_32") (pintype "input"))
    )
    (net (code "53") (name "/NAND_D4") (class "Default")
      (node (ref "U1") (pin "G1") (pinfunction "RDATA4_G1") (pintype "input"))
      (node (ref "U3") (pin "41") (pinfunction "IO4_41") (pintype "input"))
    )
    (net (code "54") (name "/NAND_D5") (class "Default")
      (node (ref "U1") (pin "K7") (pinfunction "RDATA5_K7") (pintype "input"))
      (node (ref "U3") (pin "42") (pinfunction "IO5_42") (pintype "input"))
    )
    (net (code "55") (name "/NAND_D6") (class "Default")
      (node (ref "U1") (pin "G2") (pinfunction "RDATA6_G2") (pintype "input"))
      (node (ref "U3") (pin "43") (pinfunction "IO6_43") (pintype "input"))
    )
    (net (code "56") (name "/NAND_D7") (class "Default")
      (node (ref "U1") (pin "K8") (pinfunction "RDATA7_K8") (pintype "input"))
      (node (ref "U3") (pin "44") (pinfunction "IO7_44") (pintype "input"))
    )
    (net (code "57") (name "/NAND_RE") (class "Default")
      (node (ref "U1") (pin "D1") (pinfunction "nFRE/GPA20_D1") (pintype "input"))
      (node (ref "U3") (pin "8") (pinfunction "RE_8") (pintype "input"))
    )
    (net (code "58") (name "/NAND_RNB") (class "Default")
      (node (ref "U1") (pin "E3") (pinfunction "FRnB/GPM1_E3") (pintype "input"))
      (node (ref "U3") (pin "7") (pinfunction "R/B_7") (pintype "input"))
    )
    (net (code "59") (name "/NAND_WE") (class "Default")
      (node (ref "U1") (pin "H6") (pinfunction "nFWE/GPA19_H6") (pintype "input"))
      (node (ref "U3") (pin "18") (pinfunction "WE_18") (pintype "input"))
    )
    (net (code "60") (name "/TCK") (class "Default")
      (node (ref "CN1") (pin "5") (pinfunction "5_5") (pintype "input"))
      (node (ref "R13") (pin "1") (pinfunction "1_1") (pintype "input"))
      (node (ref "U1") (pin "P20") (pinfunction "TCK_P20") (pintype "input"))
    )
    (net (code "61") (name "/TDI") (class "Default")
      (node (ref "CN1") (pin "1") (pinfunction "1_1") (pintype "input"))
      (node (ref "R10") (pin "1") (pinfunction "1_1") (pintype "input"))
      (node (ref "U1") (pin "L17") (pinfunction "TDI_L17") (pintype "input"))
    )
    (net (code "62") (name "/TDO") (class "Default")
      (node (ref "CN1") (pin "4") (pinfunction "4_4") (pintype "input"))
      (node (ref "U1") (pin "M13") (pinfunction "TDO_M13") (pintype "output"))
    )
    (net (code "63") (name "/TMS") (class "Default")
      (node (ref "CN1") (pin "2") (pinfunction "2_2") (pintype "input"))
      (node (ref "R11") (pin "1") (pinfunction "1_1") (pintype "input"))
      (node (ref "U1") (pin "P19") (pinfunction "TMS_P19") (pintype "input"))
    )
    (net (code "64") (name "/TRST") (class "Default")
      (node (ref "CN1") (pin "3") (pinfunction "3_3") (pintype "input"))
      (node (ref "R12") (pin "1") (pinfunction "1_1") (pintype "input"))
      (node (ref "U1") (pin "L15") (pinfunction "nTRST_L15") (pintype "input"))
    )
    (net (code "65") (name "/UART_RX") (class "Default")
      (node (ref "H1") (pin "2") (pinfunction "2_2") (pintype "input"))
      (node (ref "U1") (pin "V6") (pinfunction "RXD0_V6") (pintype "input"))
    )
    (net (code "66") (name "/UART_TX") (class "Default")
      (node (ref "H1") (pin "3") (pinfunction "3_3") (pintype "input"))
      (node (ref "U1") (pin "P8") (pinfunction "TXD0_P8") (pintype "output"))
    )
    (net (code "67") (name "/UDEV_CLK") (class "Default")
      (node (ref "U1") (pin "K19") (pinfunction "XI_UDEV_K19") (pintype "output"))
      (node (ref "U1") (pin "V8") (pinfunction "CLKOUT0/GPH13_V8") (pintype "input"))
    )
    (net (code "68") (name "/USB_DN") (class "Default")
      (node (ref "U1") (pin "J20") (pinfunction "DM_UDEV_J20") (pintype "bidirectional"))
      (node (ref "USB2") (pin "5") (pinfunction "DN2_5") (pintype "input"))
      (node (ref "USB2") (pin "7") (pinfunction "DN1_7") (pintype "input"))
    )
    (net (code "69") (name "/USB_DP") (class "Default")
      (node (ref "U1") (pin "H19") (pinfunction "DP_UDEV_H19") (pintype "bidirectional"))
      (node (ref "USB2") (pin "6") (pinfunction "DP1_6") (pintype "input"))
      (node (ref "USB2") (pin "8") (pinfunction "DP2_8") (pintype "input"))
    )
    (net (code "70") (name "1V2") (class "Default")
      (node (ref "C12") (pin "1") (pinfunction "1_1") (pintype "input"))
      (node (ref "C35") (pin "1") (pinfunction "1_1") (pintype "input"))
      (node (ref "C36") (pin "1") (pinfunction "1_1") (pintype "input"))
      (node (ref "U1") (pin "J19") (pinfunction "VDDI_UDEV_J19") (pintype "input"))
      (node (ref "U1") (pin "R19") (pinfunction "VDDalive_R19") (pintype "input"))
      (node (ref "U9") (pin "2") (pinfunction "VOUT_2") (pintype "input"))
    )
    (net (code "71") (name "1V3") (class "Default")
      (node (ref "C13") (pin "1") (pinfunction "1_1") (pintype "input"))
      (node (ref "C14") (pin "1") (pinfunction "1_1") (pintype "input"))
      (node (ref "C15") (pin "1") (pinfunction "1_1") (pintype "input"))
      (node (ref "C17") (pin "1") (pinfunction "1_1") (pintype "input"))
      (node (ref "C18") (pin "1") (pinfunction "1_1") (pintype "input"))
      (node (ref "C19") (pin "1") (pinfunction "1_1") (pintype "input"))
      (node (ref "C20") (pin "1") (pinfunction "1_1") (pintype "input"))
      (node (ref "C27") (pin "1") (pinfunction "1_1") (pintype "input"))
      (node (ref "C28") (pin "1") (pinfunction "1_1") (pintype "input"))
      (node (ref "C8") (pin "1") (pinfunction "1_1") (pintype "input"))
      (node (ref "U1") (pin "G11") (pinfunction "VDDi_G11") (pintype "input"))
      (node (ref "U1") (pin "G13") (pinfunction "VDDi_G13") (pintype "input"))
      (node (ref "U1") (pin "J13") (pinfunction "VDDi_J13") (pintype "input"))
      (node (ref "U1") (pin "J2") (pinfunction "VDDiarm_J2") (pintype "input"))
      (node (ref "U1") (pin "J8") (pinfunction "VDDi_J8") (pintype "input"))
      (node (ref "U1") (pin "K2") (pinfunction "VDDiarm_K2") (pintype "input"))
      (node (ref "U1") (pin "L8") (pinfunction "VDDi_L8") (pintype "input"))
      (node (ref "U1") (pin "M7") (pinfunction "VDDi_M7") (pintype "input"))
      (node (ref "U1") (pin "N14") (pinfunction "VDDi_N14") (pintype "input"))
      (node (ref "U1") (pin "N3") (pinfunction "VDDiarm_N3") (pintype "input"))
      (node (ref "U1") (pin "P10") (pinfunction "VDDi_P10") (pintype "input"))
      (node (ref "U1") (pin "R3") (pinfunction "VDDiarm_R3") (pintype "input"))
      (node (ref "U1") (pin "V5") (pinfunction "VDDiarm_V5") (pintype "input"))
      (node (ref "U1") (pin "W8") (pinfunction "VDDiarm_W8") (pintype "input"))
      (node (ref "U1") (pin "W9") (pinfunction "VDDiarm_W9") (pintype "input"))
      (node (ref "U1") (pin "Y16") (pinfunction "VDD_MPLL_Y16") (pintype "input"))
      (node (ref "U1") (pin "Y17") (pinfunction "VDD_UPLL_Y17") (pintype "input"))
      (node (ref "U7") (pin "2") (pinfunction "VOUT_2") (pintype "input"))
    )
    (net (code "72") (name "1V8") (class "Default")
      (node (ref "C10") (pin "1") (pinfunction "1_1") (pintype "input"))
      (node (ref "C22") (pin "1") (pinfunction "1_1") (pintype "input"))
      (node (ref "C23") (pin "1") (pinfunction "1_1") (pintype "input"))
      (node (ref "C24") (pin "1") (pinfunction "1_1") (pintype "input"))
      (node (ref "C25") (pin "1") (pinfunction "1_1") (pintype "input"))
      (node (ref "C26") (pin "1") (pinfunction "1_1") (pintype "input"))
      (node (ref "C37") (pin "1") (pinfunction "1_1") (pintype "input"))
      (node (ref "C38") (pin "1") (pinfunction "1_1") (pintype "input"))
      (node (ref "C39") (pin "1") (pinfunction "1_1") (pintype "input"))
      (node (ref "C4") (pin "1") (pinfunction "1_1") (pintype "input"))
      (node (ref "C40") (pin "1") (pinfunction "1_1") (pintype "input"))
      (node (ref "C41") (pin "1") (pinfunction "1_1") (pintype "input"))
      (node (ref "C42") (pin "1") (pinfunction "1_1") (pintype "input"))
      (node (ref "R3") (pin "2") (pinfunction "2_2") (pintype "input"))
      (node (ref "U1") (pin "A12") (pinfunction "VDD_SDRAM_A12") (pintype "input"))
      (node (ref "U1") (pin "C16") (pinfunction "VDD_SDRAM_C16") (pintype "input"))
      (node (ref "U1") (pin "D19") (pinfunction "VDD_SDRAM_D19") (pintype "input"))
      (node (ref "U1") (pin "H14") (pinfunction "VDD_SDRAM_H14") (pintype "input"))
      (node (ref "U1") (pin "N12") (pinfunction "VDD_SDRAM_N12") (pintype "input"))
      (node (ref "U1") (pin "P13") (pinfunction "VDD_SDRAM_P13") (pintype "input"))
      (node (ref "U4") (pin "A1") (pinfunction "VDD_A1") (pintype "input"))
      (node (ref "U4") (pin "A9") (pinfunction "VDDQ_A9") (pintype "input"))
      (node (ref "U4") (pin "C1") (pinfunction "VDDQ_C1") (pintype "input"))
      (node (ref "U4") (pin "C3") (pinfunction "VDDQ_C3") (pintype "input"))
      (node (ref "U4") (pin "C7") (pinfunction "VDDQ_C7") (pintype "input"))
      (node (ref "U4") (pin "C9") (pinfunction "VDDQ_C9") (pintype "input"))
      (node (ref "U4") (pin "E1") (pinfunction "VDD_E1") (pintype "input"))
      (node (ref "U4") (pin "E9") (pinfunction "VDDQ_E9") (pintype "input"))
      (node (ref "U4") (pin "G1") (pinfunction "VDDQ_G1") (pintype "input"))
      (node (ref "U4") (pin "G3") (pinfunction "VDDQ_G3") (pintype "input"))
      (node (ref "U4") (pin "G7") (pinfunction "VDDQ_G7") (pintype "input"))
      (node (ref "U4") (pin "G9") (pinfunction "VDDQ_G9") (pintype "input"))
      (node (ref "U4") (pin "J1") (pinfunction "VDDL_J1") (pintype "input"))
      (node (ref "U4") (pin "J9") (pinfunction "VDD_J9") (pintype "input"))
      (node (ref "U4") (pin "M9") (pinfunction "VDD_M9") (pintype "input"))
      (node (ref "U4") (pin "R1") (pinfunction "VDD_R1") (pintype "input"))
      (node (ref "U8") (pin "2") (pinfunction "VOUT_2") (pintype "input"))
    )
    (net (code "73") (name "3V3") (class "Default")
      (node (ref "C30") (pin "1") (pinfunction "1_1") (pintype "input"))
      (node (ref "C31") (pin "1") (pinfunction "1_1") (pintype "input"))
      (node (ref "C32") (pin "1") (pinfunction "1_1") (pintype "input"))
      (node (ref "C33") (pin "1") (pinfunction "1_1") (pintype "input"))
      (node (ref "C34") (pin "1") (pinfunction "1_1") (pintype "input"))
      (node (ref "C43") (pin "1") (pinfunction "1_1") (pintype "input"))
      (node (ref "C6") (pin "1") (pinfunction "1_1") (pintype "input"))
      (node (ref "CN1") (pin "6") (pinfunction "6_6") (pintype "input"))
      (node (ref "R10") (pin "2") (pinfunction "2_2") (pintype "input"))
      (node (ref "R11") (pin "2") (pinfunction "2_2") (pintype "input"))
      (node (ref "R12") (pin "2") (pinfunction "2_2") (pintype "input"))
      (node (ref "R13") (pin "2") (pinfunction "2_2") (pintype "input"))
      (node (ref "R14") (pin "2") (pinfunction "2_2") (pintype "input"))
      (node (ref "R15") (pin "2") (pinfunction "2_2") (pintype "input"))
      (node (ref "U1") (pin "C5") (pinfunction "VDD_SRAM_C5") (pintype "input"))
      (node (ref "U1") (pin "F3") (pinfunction "VDD_SRAM_F3") (pintype "input"))
      (node (ref "U1") (pin "G18") (pinfunction "VDD33_G18") (pintype "input"))
      (node (ref "U1") (pin "G19") (pinfunction "VDD33_G19") (pintype "input"))
      (node (ref "U1") (pin "H1") (pinfunction "VDD_SRAM_H1") (pintype "input"))
      (node (ref "U1") (pin "L19") (pinfunction "VDD_USBOSC_L19") (pintype "input"))
      (node (ref "U1") (pin "M18") (pinfunction "VDD_OP3_M18") (pintype "input"))
      (node (ref "U1") (pin "N4") (pinfunction "GPC7_N4") (pintype "input"))
      (node (ref "U1") (pin "P18") (pinfunction "nBATT_FLT_P18") (pintype "input"))
      (node (ref "U1") (pin "R13") (pinfunction "AIN9_R13") (pintype "input"))
      (node (ref "U1") (pin "R14") (pinfunction "VDDA_ADC_R14") (pintype "input"))
      (node (ref "U1") (pin "T19") (pinfunction "VDD_OP1_T19") (pintype "input"))
      (node (ref "U1") (pin "U15") (pinfunction "Vref_U15") (pintype "input"))
      (node (ref "U1") (pin "U16") (pinfunction "OM3_U16") (pintype "input"))
      (node (ref "U1") (pin "V14") (pinfunction "AIN7_V14") (pintype "input"))
      (node (ref "U1") (pin "W12") (pinfunction "VDD_SD_W12") (pintype "input"))
      (node (ref "U1") (pin "W19") (pinfunction "VDD_RTC_W19") (pintype "input"))
      (node (ref "U1") (pin "W20") (pinfunction "XTIrtc_W20") (pintype "input"))
      (node (ref "U1") (pin "Y6") (pinfunction "VDD_OP2_Y6") (pintype "input"))
      (node (ref "U3") (pin "12") (pinfunction "VCC_12") (pintype "input"))
      (node (ref "U3") (pin "19") (pinfunction "WP_19") (pintype "input"))
      (node (ref "U3") (pin "37") (pinfunction "VCC_37") (pintype "input"))
      (node (ref "U6") (pin "2") (pinfunction "VOUT_2") (pintype "input"))
    )
    (net (code "74") (name "5V") (class "Default")
      (node (ref "C11") (pin "1") (pinfunction "1_1") (pintype "input"))
      (node (ref "C5") (pin "1") (pinfunction "1_1") (pintype "input"))
      (node (ref "C7") (pin "1") (pinfunction "1_1") (pintype "input"))
      (node (ref "C9") (pin "1") (pinfunction "1_1") (pintype "input"))
      (node (ref "U6") (pin "3") (pinfunction "VIN_3") (pintype "input"))
      (node (ref "U7") (pin "3") (pinfunction "VIN_3") (pintype "input"))
      (node (ref "U8") (pin "3") (pinfunction "VIN_3") (pintype "input"))
      (node (ref "U9") (pin "3") (pinfunction "VIN_3") (pintype "input"))
      (node (ref "USB2") (pin "11") (pinfunction "VBUS_11") (pintype "input"))
      (node (ref "USB2") (pin "2") (pinfunction "VBUS_2") (pintype "input"))
    )
    (net (code "75") (name "GND") (class "Default")
      (node (ref "C1") (pin "1") (pinfunction "1_1") (pintype "input"))
      (node (ref "C10") (pin "2") (pinfunction "2_2") (pintype "input"))
      (node (ref "C11") (pin "2") (pinfunction "2_2") (pintype "input"))
      (node (ref "C12") (pin "2") (pinfunction "2_2") (pintype "input"))
      (node (ref "C13") (pin "2") (pinfunction "2_2") (pintype "input"))
      (node (ref "C14") (pin "2") (pinfunction "2_2") (pintype "input"))
      (node (ref "C15") (pin "2") (pinfunction "2_2") (pintype "input"))
      (node (ref "C17") (pin "2") (pinfunction "2_2") (pintype "input"))
      (node (ref "C18") (pin "2") (pinfunction "2_2") (pintype "input"))
      (node (ref "C19") (pin "2") (pinfunction "2_2") (pintype "input"))
      (node (ref "C2") (pin "1") (pinfunction "1_1") (pintype "input"))
      (node (ref "C20") (pin "2") (pinfunction "2_2") (pintype "input"))
      (node (ref "C22") (pin "2") (pinfunction "2_2") (pintype "input"))
      (node (ref "C23") (pin "2") (pinfunction "2_2") (pintype "input"))
      (node (ref "C24") (pin "2") (pinfunction "2_2") (pintype "input"))
      (node (ref "C25") (pin "2") (pinfunction "2_2") (pintype "input"))
      (node (ref "C26") (pin "2") (pinfunction "2_2") (pintype "input"))
      (node (ref "C27") (pin "2") (pinfunction "2_2") (pintype "input"))
      (node (ref "C28") (pin "2") (pinfunction "2_2") (pintype "input"))
      (node (ref "C3") (pin "1") (pinfunction "1_1") (pintype "input"))
      (node (ref "C30") (pin "2") (pinfunction "2_2") (pintype "input"))
      (node (ref "C31") (pin "2") (pinfunction "2_2") (pintype "input"))
      (node (ref "C32") (pin "2") (pinfunction "2_2") (pintype "input"))
      (node (ref "C33") (pin "2") (pinfunction "2_2") (pintype "input"))
      (node (ref "C34") (pin "2") (pinfunction "2_2") (pintype "input"))
      (node (ref "C35") (pin "2") (pinfunction "2_2") (pintype "input"))
      (node (ref "C36") (pin "2") (pinfunction "2_2") (pintype "input"))
      (node (ref "C37") (pin "2") (pinfunction "2_2") (pintype "input"))
      (node (ref "C38") (pin "2") (pinfunction "2_2") (pintype "input"))
      (node (ref "C39") (pin "2") (pinfunction "2_2") (pintype "input"))
      (node (ref "C40") (pin "2") (pinfunction "2_2") (pintype "input"))
      (node (ref "C41") (pin "2") (pinfunction "2_2") (pintype "input"))
      (node (ref "C42") (pin "2") (pinfunction "2_2") (pintype "input"))
      (node (ref "C43") (pin "2") (pinfunction "2_2") (pintype "input"))
      (node (ref "C44") (pin "2") (pinfunction "2_2") (pintype "input"))
      (node (ref "C45") (pin "2") (pinfunction "2_2") (pintype "input"))
      (node (ref "C5") (pin "2") (pinfunction "2_2") (pintype "input"))
      (node (ref "C6") (pin "2") (pinfunction "2_2") (pintype "input"))
      (node (ref "C7") (pin "2") (pinfunction "2_2") (pintype "input"))
      (node (ref "C8") (pin "2") (pinfunction "2_2") (pintype "input"))
      (node (ref "C9") (pin "2") (pinfunction "2_2") (pintype "input"))
      (node (ref "CN1") (pin "7") (pinfunction "7_7") (pintype "input"))
      (node (ref "H1") (pin "1") (pinfunction "1_1") (pintype "input"))
      (node (ref "LED1") (pin "1") (pinfunction "K_1") (pintype "input"))
      (node (ref "LED2") (pin "1") (pinfunction "K_1") (pintype "input"))
      (node (ref "LED3") (pin "1") (pinfunction "K_1") (pintype "input"))
      (node (ref "R1") (pin "2") (pinfunction "2_2") (pintype "input"))
      (node (ref "R4") (pin "1") (pinfunction "1_1") (pintype "input"))
      (node (ref "R8") (pin "1") (pinfunction "1_1") (pintype "input"))
      (node (ref "R9") (pin "1") (pinfunction "1_1") (pintype "input"))
      (node (ref "U1") (pin "B11") (pinfunction "VSS_SDRAM_B11") (pintype "input"))
      (node (ref "U1") (pin "B5") (pinfunction "VSS_SRAM_B5") (pintype "input"))
      (node (ref "U1") (pin "C15") (pinfunction "VSS_SDRAM_C15") (pintype "input"))
      (node (ref "U1") (pin "D18") (pinfunction "VSS_SDRAM_D18") (pintype "input"))
      (node (ref "U1") (pin "E2") (pinfunction "VSS_SRAM_E2") (pintype "input"))
      (node (ref "U1") (pin "H11") (pinfunction "VSSi_H11") (pintype "input"))
      (node (ref "U1") (pin "H13") (pinfunction "VSSi_H13") (pintype "input"))
      (node (ref "U1") (pin "H18") (pinfunction "VSS33T_H18") (pintype "input"))
      (node (ref "U1") (pin "J17") (pinfunction "VSS33T_J17") (pintype "input"))
      (node (ref "U1") (pin "J3") (pinfunction "VSSi_J3") (pintype "input"))
      (node (ref "U1") (pin "J7") (pinfunction "VSSi_J7") (pintype "input"))
      (node (ref "U1") (pin "K20") (pinfunction "VSSIP_UDEV_K20") (pintype "input"))
      (node (ref "U1") (pin "K3") (pinfunction "VSSiarm_K3") (pintype "input"))
      (node (ref "U1") (pin "L1") (pinfunction "GPC6_L1") (pintype "input"))
      (node (ref "U1") (pin "L20") (pinfunction "VSS33C_L20") (pintype "input"))
      (node (ref "U1") (pin "L3") (pinfunction "VSSiarm_L3") (pintype "input"))
      (node (ref "U1") (pin "L6") (pinfunction "VSSi_L6") (pintype "input"))
      (node (ref "U1") (pin "M19") (pinfunction "VSS_OP3_M19") (pintype "input"))
      (node (ref "U1") (pin "M6") (pinfunction "GPC5_M6") (pintype "input"))
      (node (ref "U1") (pin "M8") (pinfunction "VSSi_M8") (pintype "input"))
      (node (ref "U1") (pin "N10") (pinfunction "VSSi_N10") (pintype "input"))
      (node (ref "U1") (pin "N11") (pinfunction "AIN3_N11") (pintype "input"))
      (node (ref "U1") (pin "N13") (pinfunction "VSSi_N13") (pintype "input"))
      (node (ref "U1") (pin "P11") (pinfunction "VSSA_ADC_P11") (pintype "input"))
      (node (ref "U1") (pin "P12") (pinfunction "AIN5_P12") (pintype "input"))
      (node (ref "U1") (pin "P15") (pinfunction "EXTCLK_P15") (pintype "input"))
      (node (ref "U1") (pin "P3") (pinfunction "VSSiarm_P3") (pintype "input"))
      (node (ref "U1") (pin "P4") (pinfunction "VSSiarm_P4") (pintype "input"))
      (node (ref "U1") (pin "R17") (pinfunction "OM0_R17") (pintype "input"))
      (node (ref "U1") (pin "R20") (pinfunction "VSSalive_R20") (pintype "input"))
      (node (ref "U1") (pin "T20") (pinfunction "VSS_OP1_T20") (pintype "input"))
      (node (ref "U1") (pin "U14") (pinfunction "AIN1_U14") (pintype "input"))
      (node (ref "U1") (pin "U17") (pinfunction "OM1_U17") (pintype "input"))
      (node (ref "U1") (pin "U7") (pinfunction "VSSiarm_U7") (pintype "input"))
      (node (ref "U1") (pin "U8") (pinfunction "VSSiarm_U8") (pintype "input"))
      (node (ref "U1") (pin "U9") (pinfunction "VSSiarm_U9") (pintype "input"))
      (node (ref "U1") (pin "V15") (pinfunction "VSS_MPLL_V15") (pintype "input"))
      (node (ref "U1") (pin "V17") (pinfunction "AIN6_V17") (pintype "input"))
      (node (ref "U1") (pin "V18") (pinfunction "OM4_V18") (pintype "input"))
      (node (ref "U1") (pin "V19") (pinfunction "OM2_V19") (pintype "input"))
      (node (ref "U1") (pin "W16") (pinfunction "VSS_UPLL_W16") (pintype "input"))
      (node (ref "U1") (pin "W17") (pinfunction "AIN8_W17") (pintype "input"))
      (node (ref "U1") (pin "W18") (pinfunction "AIN2_W18") (pintype "input"))
      (node (ref "U1") (pin "W7") (pinfunction "VSS_OP2_W7") (pintype "input"))
      (node (ref "U1") (pin "Y13") (pinfunction "VSS_SD_Y13") (pintype "input"))
      (node (ref "U1") (pin "Y18") (pinfunction "AIN4_Y18") (pintype "input"))
      (node (ref "U1") (pin "Y19") (pinfunction "AIN0_Y19") (pintype "input"))
      (node (ref "U3") (pin "13") (pinfunction "VSS_13") (pintype "input"))
      (node (ref "U3") (pin "36") (pinfunction "VSS_36") (pintype "input"))
      (node (ref "U4") (pin "A3") (pinfunction "VSS_A3") (pintype "input"))
      (node (ref "U4") (pin "A7") (pinfunction "VSSQ_A7") (pintype "input"))
      (node (ref "U4") (pin "B2") (pinfunction "VSSQ_B2") (pintype "input"))
      (node (ref "U4") (pin "B8") (pinfunction "VSSQ_B8") (pintype "input"))
      (node (ref "U4") (pin "D2") (pinfunction "VSSQ_D2") (pintype "input"))
      (node (ref "U4") (pin "D8") (pinfunction "VSSQ_D8") (pintype "input"))
      (node (ref "U4") (pin "E3") (pinfunction "VSS_E3") (pintype "input"))
      (node (ref "U4") (pin "E7") (pinfunction "VSSQ_E7") (pintype "input"))
      (node (ref "U4") (pin "F2") (pinfunction "VSSQ_F2") (pintype "input"))
      (node (ref "U4") (pin "F8") (pinfunction "VSSQ_F8") (pintype "input"))
      (node (ref "U4") (pin "H2") (pinfunction "VSSQ_H2") (pintype "input"))
      (node (ref "U4") (pin "H8") (pinfunction "VSSQ_H8") (pintype "input"))
      (node (ref "U4") (pin "J3") (pinfunction "VSS_J3") (pintype "input"))
      (node (ref "U4") (pin "J7") (pinfunction "VSSDL_J7") (pintype "input"))
      (node (ref "U4") (pin "K9") (pinfunction "ODT_K9") (pintype "input"))
      (node (ref "U4") (pin "L1") (pinfunction "NC_L1") (pintype "input"))
      (node (ref "U4") (pin "N1") (pinfunction "VSS_N1") (pintype "input"))
      (node (ref "U4") (pin "P9") (pinfunction "VSS_P9") (pintype "input"))
      (node (ref "U6") (pin "1") (pinfunction "VSS_1") (pintype "input"))
      (node (ref "U7") (pin "1") (pinfunction "VSS_1") (pintype "input"))
      (node (ref "U8") (pin "1") (pinfunction "VSS_1") (pintype "input"))
      (node (ref "U9") (pin "1") (pinfunction "VSS_1") (pintype "input"))
      (node (ref "USB2") (pin "1") (pinfunction "GND_1") (pintype "input"))
      (node (ref "USB2") (pin "12") (pinfunction "GND_12") (pintype "input"))
      (node (ref "USB2") (pin "13") (pinfunction "SHELL_13") (pintype "input"))
      (node (ref "USB2") (pin "14") (pinfunction "SHELL_14") (pintype "input"))
    )
    (net (code "76") (name "Net-(LED1-A)") (class "Default")
      (node (ref "LED1") (pin "2") (pinfunction "A_2") (pintype "input"))
      (node (ref "R5") (pin "2") (pinfunction "2_2") (pintype "input"))
    )
    (net (code "77") (name "Net-(LED2-A)") (class "Default")
      (node (ref "LED2") (pin "2") (pinfunction "A_2") (pintype "input"))
      (node (ref "R6") (pin "2") (pinfunction "2_2") (pintype "input"))
    )
    (net (code "78") (name "Net-(LED3-A)") (class "Default")
      (node (ref "LED3") (pin "2") (pinfunction "A_2") (pintype "input"))
      (node (ref "R7") (pin "2") (pinfunction "2_2") (pintype "input"))
    )
    (net (code "79") (name "Net-(U1-REXT)") (class "Default")
      (node (ref "R1") (pin "1") (pinfunction "1_1") (pintype "input"))
      (node (ref "U1") (pin "H20") (pinfunction "REXT_H20") (pintype "output"))
    )
    (net (code "80") (name "Net-(U1-UPLLCAP)") (class "Default")
      (node (ref "C45") (pin "1") (pinfunction "1_1") (pintype "input"))
      (node (ref "U1") (pin "V16") (pinfunction "UPLLCAP_V16") (pintype "input"))
    )
    (net (code "81") (name "Net-(U1-XTIpll)") (class "Default")
      (node (ref "C1") (pin "2") (pinfunction "2_2") (pintype "input"))
      (node (ref "U1") (pin "V20") (pinfunction "XTIpll_V20") (pintype "input"))
      (node (ref "X2") (pin "2") (pinfunction "OSC2_2") (pintype "input"))
    )
    (net (code "82") (name "Net-(U1-XTOpll)") (class "Default")
      (node (ref "C2") (pin "2") (pinfunction "2_2") (pintype "input"))
      (node (ref "U1") (pin "U18") (pinfunction "XTOpll_U18") (pintype "output"))
      (node (ref "X2") (pin "1") (pinfunction "OSC1_1") (pintype "input"))
    )
    (net (code "83") (name "Net-(U1-nRESET)") (class "Default")
      (node (ref "C44") (pin "1") (pinfunction "1_1") (pintype "input"))
      (node (ref "R14") (pin "1") (pinfunction "1_1") (pintype "input"))
      (node (ref "U1") (pin "M14") (pinfunction "nRESET_M14") (pintype "input"))
    )
    (net (code "84") (name "Net-(U1-nWAIT)") (class "Default")
      (node (ref "R15") (pin "1") (pinfunction "1_1") (pintype "input"))
      (node (ref "U1") (pin "D3") (pinfunction "nWAIT_D3") (pintype "input"))
    )
    (net (code "85") (name "Net-(U4-VREF)") (class "Default")
      (node (ref "C3") (pin "2") (pinfunction "2_2") (pintype "input"))
      (node (ref "C4") (pin "2") (pinfunction "2_2") (pintype "input"))
      (node (ref "R3") (pin "1") (pinfunction "1_1") (pintype "input"))
      (node (ref "R4") (pin "2") (pinfunction "2_2") (pintype "input"))
      (node (ref "U4") (pin "J2") (pinfunction "VREF_J2") (pintype "input"))
    )
    (net (code "86") (name "Net-(USB2-CC1)") (class "Default")
      (node (ref "R8") (pin "2") (pinfunction "2_2") (pintype "input"))
      (node (ref "USB2") (pin "4") (pinfunction "CC1_4") (pintype "input"))
    )
    (net (code "87") (name "Net-(USB2-CC2)") (class "Default")
      (node (ref "R9") (pin "2") (pinfunction "2_2") (pintype "input"))
      (node (ref "USB2") (pin "10") (pinfunction "CC2_10") (pintype "input"))
    )
    (net (code "88") (name "unconnected-(CN1-Pad8)") (class "Default")
      (node (ref "CN1") (pin "8") (pinfunction "8_8") (pintype "input"))
    )
    (net (code "89") (name "unconnected-(CN1-Pad9)") (class "Default")
      (node (ref "CN1") (pin "9") (pinfunction "9_9") (pintype "input"))
    )
    (net (code "90") (name "unconnected-(U1-CLKOUT1{slash}GPH14-PadY7)") (class "Default")
      (node (ref "U1") (pin "Y7") (pinfunction "CLKOUT1/GPH14_Y7") (pintype "input+no_connect"))
    )
    (net (code "91") (name "unconnected-(U1-DQM2{slash}GPA25-PadB16)") (class "Default")
      (node (ref "U1") (pin "B16") (pinfunction "DQM2/GPA25_B16") (pintype "input+no_connect"))
    )
    (net (code "92") (name "unconnected-(U1-DQM3{slash}GPA26-PadD14)") (class "Default")
      (node (ref "U1") (pin "D14") (pinfunction "DQM3/GPA26_D14") (pintype "input+no_connect"))
    )
    (net (code "93") (name "unconnected-(U1-PWR_EN-PadM15)") (class "Default")
      (node (ref "U1") (pin "M15") (pinfunction "PWR_EN_M15") (pintype "input+no_connect"))
    )
    (net (code "94") (name "unconnected-(U1-RADDR0{slash}GPA0-PadB3)") (class "Default")
      (node (ref "U1") (pin "B3") (pinfunction "RADDR0/GPA0_B3") (pintype "input+no_connect"))
    )
    (net (code "95") (name "unconnected-(U1-RADDR1-PadD7)") (class "Default")
      (node (ref "U1") (pin "D7") (pinfunction "RADDR1_D7") (pintype "input+no_connect"))
    )
    (net (code "96") (name "unconnected-(U1-RADDR2-PadA3)") (class "Default")
      (node (ref "U1") (pin "A3") (pinfunction "RADDR2_A3") (pintype "input+no_connect"))
    )
    (net (code "97") (name "unconnected-(U1-RADDR3-PadH8)") (class "Default")
      (node (ref "U1") (pin "H8") (pinfunction "RADDR3_H8") (pintype "input+no_connect"))
    )
    (net (code "98") (name "unconnected-(U1-RADDR4-PadC4)") (class "Default")
      (node (ref "U1") (pin "C4") (pinfunction "RADDR4_C4") (pintype "input+no_connect"))
    )
    (net (code "99") (name "unconnected-(U1-RADDR5-PadG8)") (class "Default")
      (node (ref "U1") (pin "G8") (pinfunction "RADDR5_G8") (pintype "input+no_connect"))
    )
    (net (code "100") (name "unconnected-(U1-RADDR6-PadB4)") (class "Default")
      (node (ref "U1") (pin "B4") (pinfunction "RADDR6_B4") (pintype "input+no_connect"))
    )
    (net (code "101") (name "unconnected-(U1-RADDR7-PadF8)") (class "Default")
      (node (ref "U1") (pin "F8") (pinfunction "RADDR7_F8") (pintype "input+no_connect"))
    )
    (net (code "102") (name "unconnected-(U1-RADDR8-PadA4)") (class "Default")
      (node (ref "U1") (pin "A4") (pinfunction "RADDR8_A4") (pintype "input+no_connect"))
    )
    (net (code "103") (name "unconnected-(U1-RADDR9-PadD8)") (class "Default")
      (node (ref "U1") (pin "D8") (pinfunction "RADDR9_D8") (pintype "input+no_connect"))
    )
    (net (code "104") (name "unconnected-(U1-RADDR10-PadA5)") (class "Default")
      (node (ref "U1") (pin "A5") (pinfunction "RADDR10_A5") (pintype "input+no_connect"))
    )
    (net (code "105") (name "unconnected-(U1-RADDR11-PadH9)") (class "Default")
      (node (ref "U1") (pin "H9") (pinfunction "RADDR11_H9") (pintype "input+no_connect"))
    )
    (net (code "106") (name "unconnected-(U1-RADDR12-PadC6)") (class "Default")
      (node (ref "U1") (pin "C6") (pinfunction "RADDR12_C6") (pintype "input+no_connect"))
    )
    (net (code "107") (name "unconnected-(U1-RADDR13-PadG9)") (class "Default")
      (node (ref "U1") (pin "G9") (pinfunction "RADDR13_G9") (pintype "input+no_connect"))
    )
    (net (code "108") (name "unconnected-(U1-RADDR14-PadB6)") (class "Default")
      (node (ref "U1") (pin "B6") (pinfunction "RADDR14_B6") (pintype "input+no_connect"))
    )
    (net (code "109") (name "unconnected-(U1-RADDR15-PadF9)") (class "Default")
      (node (ref "U1") (pin "F9") (pinfunction "RADDR15_F9") (pintype "input+no_connect"))
    )
    (net (code "110") (name "unconnected-(U1-RADDR16{slash}GPA1-PadA6)") (class "Default")
      (node (ref "U1") (pin "A6") (pinfunction "RADDR16/GPA1_A6") (pintype "input+no_connect"))
    )
    (net (code "111") (name "unconnected-(U1-RADDR17{slash}GPA2-PadD9)") (class "Default")
      (node (ref "U1") (pin "D9") (pinfunction "RADDR17/GPA2_D9") (pintype "input+no_connect"))
    )
    (net (code "112") (name "unconnected-(U1-RADDR18{slash}GPA3-PadC7)") (class "Default")
      (node (ref "U1") (pin "C7") (pinfunction "RADDR18/GPA3_C7") (pintype "input+no_connect"))
    )
    (net (code "113") (name "unconnected-(U1-RADDR19{slash}GPA4-PadC9)") (class "Default")
      (node (ref "U1") (pin "C9") (pinfunction "RADDR19/GPA4_C9") (pintype "input+no_connect"))
    )
    (net (code "114") (name "unconnected-(U1-RADDR20{slash}GPA5-PadB7)") (class "Default")
      (node (ref "U1") (pin "B7") (pinfunction "RADDR20/GPA5_B7") (pintype "input+no_connect"))
    )
    (net (code "115") (name "unconnected-(U1-RADDR21{slash}GPA6-PadH10)") (class "Default")
      (node (ref "U1") (pin "H10") (pinfunction "RADDR21/GPA6_H10") (pintype "input+no_connect"))
    )
    (net (code "116") (name "unconnected-(U1-RADDR22{slash}GPA7-PadA7)") (class "Default")
      (node (ref "U1") (pin "A7") (pinfunction "RADDR22/GPA7_A7") (pintype "input+no_connect"))
    )
    (net (code "117") (name "unconnected-(U1-RADDR23{slash}GPA8-PadG10)") (class "Default")
      (node (ref "U1") (pin "G10") (pinfunction "RADDR23/GPA8_G10") (pintype "input+no_connect"))
    )
    (net (code "118") (name "unconnected-(U1-RADDR24{slash}GPA9-PadC8)") (class "Default")
      (node (ref "U1") (pin "C8") (pinfunction "RADDR24/GPA9_C8") (pintype "input+no_connect"))
    )
    (net (code "119") (name "unconnected-(U1-RADDR25{slash}RDATA_OEN-PadF10)") (class "Default")
      (node (ref "U1") (pin "F10") (pinfunction "RADDR25/RDATA_OEN_F10") (pintype "input+no_connect"))
    )
    (net (code "120") (name "unconnected-(U1-RDATA8-PadG3)") (class "Default")
      (node (ref "U1") (pin "G3") (pinfunction "RDATA8_G3") (pintype "input+no_connect"))
    )
    (net (code "121") (name "unconnected-(U1-RDATA9-PadK4)") (class "Default")
      (node (ref "U1") (pin "K4") (pinfunction "RDATA9_K4") (pintype "input+no_connect"))
    )
    (net (code "122") (name "unconnected-(U1-RDATA10-PadF1)") (class "Default")
      (node (ref "U1") (pin "F1") (pinfunction "RDATA10_F1") (pintype "input+no_connect"))
    )
    (net (code "123") (name "unconnected-(U1-RDATA11-PadJ6)") (class "Default")
      (node (ref "U1") (pin "J6") (pinfunction "RDATA11_J6") (pintype "input+no_connect"))
    )
    (net (code "124") (name "unconnected-(U1-RDATA12-PadF2)") (class "Default")
      (node (ref "U1") (pin "F2") (pinfunction "RDATA12_F2") (pintype "input+no_connect"))
    )
    (net (code "125") (name "unconnected-(U1-RDATA13-PadJ4)") (class "Default")
      (node (ref "U1") (pin "J4") (pinfunction "RDATA13_J4") (pintype "input+no_connect"))
    )
    (net (code "126") (name "unconnected-(U1-RDATA14-PadE1)") (class "Default")
      (node (ref "U1") (pin "E1") (pinfunction "RDATA14_E1") (pintype "input+no_connect"))
    )
    (net (code "127") (name "unconnected-(U1-RDATA15-PadH7)") (class "Default")
      (node (ref "U1") (pin "H7") (pinfunction "RDATA15_H7") (pintype "input+no_connect"))
    )
    (net (code "128") (name "unconnected-(U1-RSMBWAIT{slash}GPM0-PadC2)") (class "Default")
      (node (ref "U1") (pin "C2") (pinfunction "RSMBWAIT/GPM0_C2") (pintype "input+no_connect"))
    )
    (net (code "129") (name "unconnected-(U1-RSMCLK{slash}GPA23-PadB1)") (class "Default")
      (node (ref "U1") (pin "B1") (pinfunction "RSMCLK/GPA23_B1") (pintype "input+no_connect"))
    )
    (net (code "130") (name "unconnected-(U1-RSMVAD{slash}GPA24-PadE4)") (class "Default")
      (node (ref "U1") (pin "E4") (pinfunction "RSMVAD/GPA24_E4") (pintype "input+no_connect"))
    )
    (net (code "131") (name "unconnected-(U1-SADDR13-PadA9)") (class "Default")
      (node (ref "U1") (pin "A9") (pinfunction "SADDR13_A9") (pintype "input+no_connect"))
    )
    (net (code "132") (name "unconnected-(U1-SDATA16{slash}GPK0-PadD20)") (class "Default")
      (node (ref "U1") (pin "D20") (pinfunction "SDATA16/GPK0_D20") (pintype "input+no_connect"))
    )
    (net (code "133") (name "unconnected-(U1-SDATA17{slash}GPK1-PadF17)") (class "Default")
      (node (ref "U1") (pin "F17") (pinfunction "SDATA17/GPK1_F17") (pintype "input+no_connect"))
    )
    (net (code "134") (name "unconnected-(U1-SDATA18{slash}GPK2-PadE18)") (class "Default")
      (node (ref "U1") (pin "E18") (pinfunction "SDATA18/GPK2_E18") (pintype "input+no_connect"))
    )
    (net (code "135") (name "unconnected-(U1-SDATA19{slash}GPK3-PadG15)") (class "Default")
      (node (ref "U1") (pin "G15") (pinfunction "SDATA19/GPK3_G15") (pintype "input+no_connect"))
    )
    (net (code "136") (name "unconnected-(U1-SDATA20{slash}GPK4-PadE19)") (class "Default")
      (node (ref "U1") (pin "E19") (pinfunction "SDATA20/GPK4_E19") (pintype "input+no_connect"))
    )
    (net (code "137") (name "unconnected-(U1-SDATA21{slash}GPK5-PadG17)") (class "Default")
      (node (ref "U1") (pin "G17") (pinfunction "SDATA21/GPK5_G17") (pintype "input+no_connect"))
    )
    (net (code "138") (name "unconnected-(U1-SDATA22{slash}GPK6-PadE20)") (class "Default")
      (node (ref "U1") (pin "E20") (pinfunction "SDATA22/GPK6_E20") (pintype "input+no_connect"))
    )
    (net (code "139") (name "unconnected-(U1-SDATA23{slash}GPK7-PadH15)") (class "Default")
      (node (ref "U1") (pin "H15") (pinfunction "SDATA23/GPK7_H15") (pintype "input+no_connect"))
    )
    (net (code "140") (name "unconnected-(U1-SDATA24{slash}GPK8-PadF18)") (class "Default")
      (node (ref "U1") (pin "F18") (pinfunction "SDATA24/GPK8_F18") (pintype "input+no_connect"))
    )
    (net (code "141") (name "unconnected-(U1-SDATA25{slash}GPK9-PadH17)") (class "Default")
      (node (ref "U1") (pin "H17") (pinfunction "SDATA25/GPK9_H17") (pintype "input+no_connect"))
    )
    (net (code "142") (name "unconnected-(U1-SDATA26{slash}GPK10-PadF19)") (class "Default")
      (node (ref "U1") (pin "F19") (pinfunction "SDATA26/GPK10_F19") (pintype "input+no_connect"))
    )
    (net (code "143") (name "unconnected-(U1-SDATA27{slash}GPK11-PadJ14)") (class "Default")
      (node (ref "U1") (pin "J14") (pinfunction "SDATA27/GPK11_J14") (pintype "input+no_connect"))
    )
    (net (code "144") (name "unconnected-(U1-SDATA28{slash}GPK12-PadF20)") (class "Default")
      (node (ref "U1") (pin "F20") (pinfunction "SDATA28/GPK12_F20") (pintype "input+no_connect"))
    )
    (net (code "145") (name "unconnected-(U1-SDATA29{slash}GPK13-PadJ15)") (class "Default")
      (node (ref "U1") (pin "J15") (pinfunction "SDATA29/GPK13_J15") (pintype "input+no_connect"))
    )
    (net (code "146") (name "unconnected-(U1-SDATA30{slash}GPK14-PadG20)") (class "Default")
      (node (ref "U1") (pin "G20") (pinfunction "SDATA30/GPK14_G20") (pintype "input+no_connect"))
    )
    (net (code "147") (name "unconnected-(U1-SDATA31{slash}GPK15-PadJ18)") (class "Default")
      (node (ref "U1") (pin "J18") (pinfunction "SDATA31/GPK15_J18") (pintype "input+no_connect"))
    )
    (net (code "148") (name "unconnected-(U1-TOUT3{slash}GPB3-PadW1)") (class "Default")
      (node (ref "U1") (pin "W1") (pinfunction "TOUT3/GPB3_W1") (pintype "input+no_connect"))
    )
    (net (code "149") (name "unconnected-(U1-XO_UDEV-PadK18)") (class "Default")
      (node (ref "U1") (pin "K18") (pinfunction "XO_UDEV_K18") (pintype "output+no_connect"))
    )
    (net (code "150") (name "unconnected-(U1-XTOrtc-PadT17)") (class "Default")
      (node (ref "U1") (pin "T17") (pinfunction "XTOrtc_T17") (pintype "output+no_connect"))
    )
    (net (code "151") (name "unconnected-(U1-nRBE0-PadC3)") (class "Default")
      (node (ref "U1") (pin "C3") (pinfunction "nRBE0_C3") (pintype "input+no_connect"))
    )
    (net (code "152") (name "unconnected-(U1-nRBE1-PadF7)") (class "Default")
      (node (ref "U1") (pin "F7") (pinfunction "nRBE1_F7") (pintype "input+no_connect"))
    )
    (net (code "153") (name "unconnected-(U1-nRCS0-PadD5)") (class "Default")
      (node (ref "U1") (pin "D5") (pinfunction "nRCS0_D5") (pintype "input+no_connect"))
    )
    (net (code "154") (name "unconnected-(U1-nRCS1{slash}GPA12-PadB2)") (class "Default")
      (node (ref "U1") (pin "B2") (pinfunction "nRCS1/GPA12_B2") (pintype "input+no_connect"))
    )
    (net (code "155") (name "unconnected-(U1-nRCS2{slash}GPA13-PadD4)") (class "Default")
      (node (ref "U1") (pin "D4") (pinfunction "nRCS2/GPA13_D4") (pintype "input+no_connect"))
    )
    (net (code "156") (name "unconnected-(U1-nRCS3{slash}GPA14-PadF4)") (class "Default")
      (node (ref "U1") (pin "F4") (pinfunction "nRCS3/GPA14_F4") (pintype "input+no_connect"))
    )
    (net (code "157") (name "unconnected-(U1-nRCS4{slash}GPA15-PadC1)") (class "Default")
      (node (ref "U1") (pin "C1") (pinfunction "nRCS4/GPA15_C1") (pintype "input+no_connect"))
    )
    (net (code "158") (name "unconnected-(U1-nRCS5{slash}GPA16-PadG6)") (class "Default")
      (node (ref "U1") (pin "G6") (pinfunction "nRCS5/GPA16_G6") (pintype "input+no_connect"))
    )
    (net (code "159") (name "unconnected-(U1-nROE-PadD6)") (class "Default")
      (node (ref "U1") (pin "D6") (pinfunction "nROE_D6") (pintype "input+no_connect"))
    )
    (net (code "160") (name "unconnected-(U1-nRSTOUT{slash}GPA21-PadN18)") (class "Default")
      (node (ref "U1") (pin "N18") (pinfunction "nRSTOUT/GPA21_N18") (pintype "input+no_connect"))
    )
    (net (code "161") (name "unconnected-(U1-nRWE-PadA2)") (class "Default")
      (node (ref "U1") (pin "A2") (pinfunction "nRWE_A2") (pintype "input+no_connect"))
    )
    (net (code "162") (name "unconnected-(U1-nSCS1-PadB15)") (class "Default")
      (node (ref "U1") (pin "B15") (pinfunction "nSCS1_B15") (pintype "input+no_connect"))
    )
    (net (code "163") (name "unconnected-(U1-nXBACK{slash}GPB5-PadU6)") (class "Default")
      (node (ref "U1") (pin "U6") (pinfunction "nXBACK/GPB5_U6") (pintype "input+no_connect"))
    )
    (net (code "164") (name "unconnected-(U1-nXBREQ{slash}RTCK{slash}GPB6-PadV4)") (class "Default")
      (node (ref "U1") (pin "V4") (pinfunction "nXBREQ/RTCK/GPB6_V4") (pintype "input+no_connect"))
    )
    (net (code "165") (name "unconnected-(U1-nXDACK0{slash}I2S0_SDO1{slash}GPB9-PadW4)") (class "Default")
      (node (ref "U1") (pin "W4") (pinfunction "nXDACK0/I2S0_SDO1/GPB9_W4") (pintype "input+no_connect"))
    )
    (net (code "166") (name "unconnected-(U1-nXDREQ0{slash}I2S0_SDO2{slash}GPB10-PadU5)") (class "Default")
      (node (ref "U1") (pin "U5") (pinfunction "nXDREQ0/I2S0_SDO2/GPB10_U5") (pintype "input+no_connect"))
    )
    (net (code "167") (name "unconnected-(U3-NC-Pad1)") (class "Default")
      (node (ref "U3") (pin "1") (pinfunction "NC_1") (pintype "input+no_connect"))
    )
    (net (code "168") (name "unconnected-(U3-NC-Pad2)") (class "Default")
      (node (ref "U3") (pin "2") (pinfunction "NC_2") (pintype "input+no_connect"))
    )
    (net (code "169") (name "unconnected-(U3-NC-Pad3)") (class "Default")
      (node (ref "U3") (pin "3") (pinfunction "NC_3") (pintype "input+no_connect"))
    )
    (net (code "170") (name "unconnected-(U3-NC-Pad4)") (class "Default")
      (node (ref "U3") (pin "4") (pinfunction "NC_4") (pintype "input+no_connect"))
    )
    (net (code "171") (name "unconnected-(U3-NC-Pad5)") (class "Default")
      (node (ref "U3") (pin "5") (pinfunction "NC_5") (pintype "input+no_connect"))
    )
    (net (code "172") (name "unconnected-(U3-NC-Pad6)") (class "Default")
      (node (ref "U3") (pin "6") (pinfunction "NC_6") (pintype "input+no_connect"))
    )
    (net (code "173") (name "unconnected-(U3-NC-Pad10)") (class "Default")
      (node (ref "U3") (pin "10") (pinfunction "NC_10") (pintype "input+no_connect"))
    )
    (net (code "174") (name "unconnected-(U3-NC-Pad11)") (class "Default")
      (node (ref "U3") (pin "11") (pinfunction "NC_11") (pintype "input+no_connect"))
    )
    (net (code "175") (name "unconnected-(U3-NC-Pad14)") (class "Default")
      (node (ref "U3") (pin "14") (pinfunction "NC_14") (pintype "input+no_connect"))
    )
    (net (code "176") (name "unconnected-(U3-NC-Pad15)") (class "Default")
      (node (ref "U3") (pin "15") (pinfunction "NC_15") (pintype "input+no_connect"))
    )
    (net (code "177") (name "unconnected-(U3-NC-Pad20)") (class "Default")
      (node (ref "U3") (pin "20") (pinfunction "NC_20") (pintype "input+no_connect"))
    )
    (net (code "178") (name "unconnected-(U3-NC-Pad21)") (class "Default")
      (node (ref "U3") (pin "21") (pinfunction "NC_21") (pintype "input+no_connect"))
    )
    (net (code "179") (name "unconnected-(U3-NC-Pad22)") (class "Default")
      (node (ref "U3") (pin "22") (pinfunction "NC_22") (pintype "input+no_connect"))
    )
    (net (code "180") (name "unconnected-(U3-NC-Pad23)") (class "Default")
      (node (ref "U3") (pin "23") (pinfunction "NC_23") (pintype "input+no_connect"))
    )
    (net (code "181") (name "unconnected-(U3-NC-Pad24)") (class "Default")
      (node (ref "U3") (pin "24") (pinfunction "NC_24") (pintype "input+no_connect"))
    )
    (net (code "182") (name "unconnected-(U3-NC-Pad25)") (class "Default")
      (node (ref "U3") (pin "25") (pinfunction "NC_25") (pintype "input+no_connect"))
    )
    (net (code "183") (name "unconnected-(U3-NC-Pad26)") (class "Default")
      (node (ref "U3") (pin "26") (pinfunction "NC_26") (pintype "input+no_connect"))
    )
    (net (code "184") (name "unconnected-(U3-NC-Pad27)") (class "Default")
      (node (ref "U3") (pin "27") (pinfunction "NC_27") (pintype "input+no_connect"))
    )
    (net (code "185") (name "unconnected-(U3-NC-Pad28)") (class "Default")
      (node (ref "U3") (pin "28") (pinfunction "NC_28") (pintype "input+no_connect"))
    )
    (net (code "186") (name "unconnected-(U3-NC-Pad33)") (class "Default")
      (node (ref "U3") (pin "33") (pinfunction "NC_33") (pintype "input+no_connect"))
    )
    (net (code "187") (name "unconnected-(U3-NC-Pad34)") (class "Default")
      (node (ref "U3") (pin "34") (pinfunction "NC_34") (pintype "input+no_connect"))
    )
    (net (code "188") (name "unconnected-(U3-NC-Pad35)") (class "Default")
      (node (ref "U3") (pin "35") (pinfunction "NC_35") (pintype "input+no_connect"))
    )
    (net (code "189") (name "unconnected-(U3-NC-Pad38)") (class "Default")
      (node (ref "U3") (pin "38") (pinfunction "NC_38") (pintype "input+no_connect"))
    )
    (net (code "190") (name "unconnected-(U3-NC-Pad39)") (class "Default")
      (node (ref "U3") (pin "39") (pinfunction "NC_39") (pintype "input+no_connect"))
    )
    (net (code "191") (name "unconnected-(U3-NC-Pad40)") (class "Default")
      (node (ref "U3") (pin "40") (pinfunction "NC_40") (pintype "input+no_connect"))
    )
    (net (code "192") (name "unconnected-(U3-NC-Pad45)") (class "Default")
      (node (ref "U3") (pin "45") (pinfunction "NC_45") (pintype "input+no_connect"))
    )
    (net (code "193") (name "unconnected-(U3-NC-Pad46)") (class "Default")
      (node (ref "U3") (pin "46") (pinfunction "NC_46") (pintype "input+no_connect"))
    )
    (net (code "194") (name "unconnected-(U3-NC-Pad47)") (class "Default")
      (node (ref "U3") (pin "47") (pinfunction "NC_47") (pintype "input+no_connect"))
    )
    (net (code "195") (name "unconnected-(U3-NC-Pad48)") (class "Default")
      (node (ref "U3") (pin "48") (pinfunction "NC_48") (pintype "input+no_connect"))
    )
    (net (code "196") (name "unconnected-(U4-LDQS#-PadE8)") (class "Default")
      (node (ref "U4") (pin "E8") (pinfunction "LDQS#_E8") (pintype "input+no_connect"))
    )
    (net (code "197") (name "unconnected-(U4-NC-PadA2)") (class "Default")
      (node (ref "U4") (pin "A2") (pinfunction "NC_A2") (pintype "input+no_connect"))
    )
    (net (code "198") (name "unconnected-(U4-NC-PadE2)") (class "Default")
      (node (ref "U4") (pin "E2") (pinfunction "NC_E2") (pintype "input+no_connect"))
    )
    (net (code "199") (name "unconnected-(U4-NC-PadR3)") (class "Default")
      (node (ref "U4") (pin "R3") (pinfunction "NC_R3") (pintype "input+no_connect"))
    )
    (net (code "200") (name "unconnected-(U4-NC-PadR7)") (class "Default")
      (node (ref "U4") (pin "R7") (pinfunction "NC_R7") (pintype "input+no_connect"))
    )
    (net (code "201") (name "unconnected-(U4-NC-PadR8)") (class "Default")
      (node (ref "U4") (pin "R8") (pinfunction "NC_R8") (pintype "input+no_connect"))
    )
    (net (code "202") (name "unconnected-(U4-UDQS#-PadA8)") (class "Default")
      (node (ref "U4") (pin "A8") (pinfunction "UDQS#_A8") (pintype "input+no_connect"))
    )
    (net (code "203") (name "unconnected-(USB2-SBU1-Pad9)") (class "Default")
      (node (ref "USB2") (pin "9") (pinfunction "SBU1_9") (pintype "input"))
    )
    (net (code "204") (name "unconnected-(USB2-SBU2-Pad3)") (class "Default")
      (node (ref "USB2") (pin "3") (pinfunction "SBU2_3") (pintype "input"))
    )
  )
)
